# 2017_IHM.net
KiCad netlist of a schematic drawn in Altium Designer
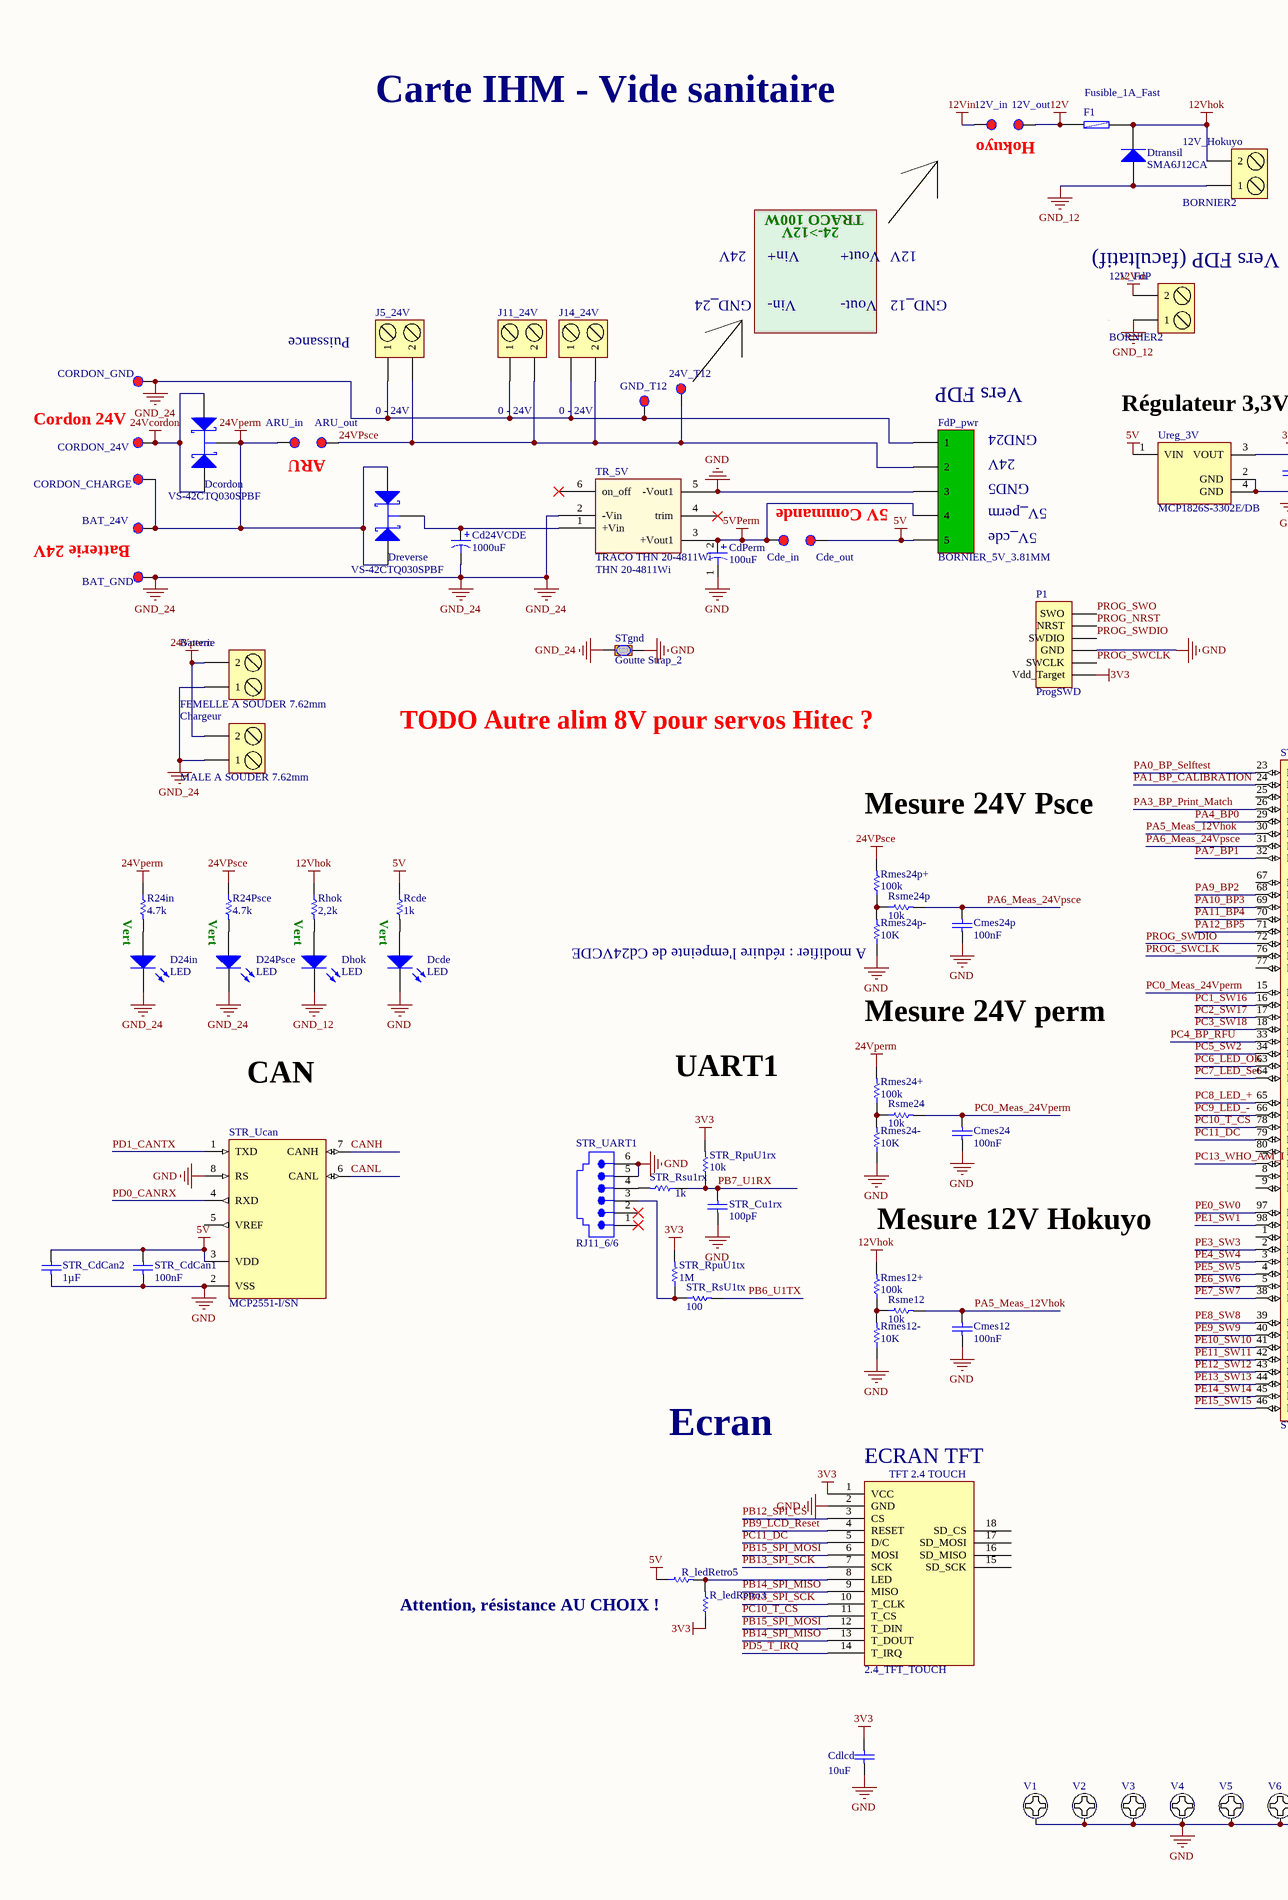
[diagram p0: 2017_IHM.SchDoc, left]
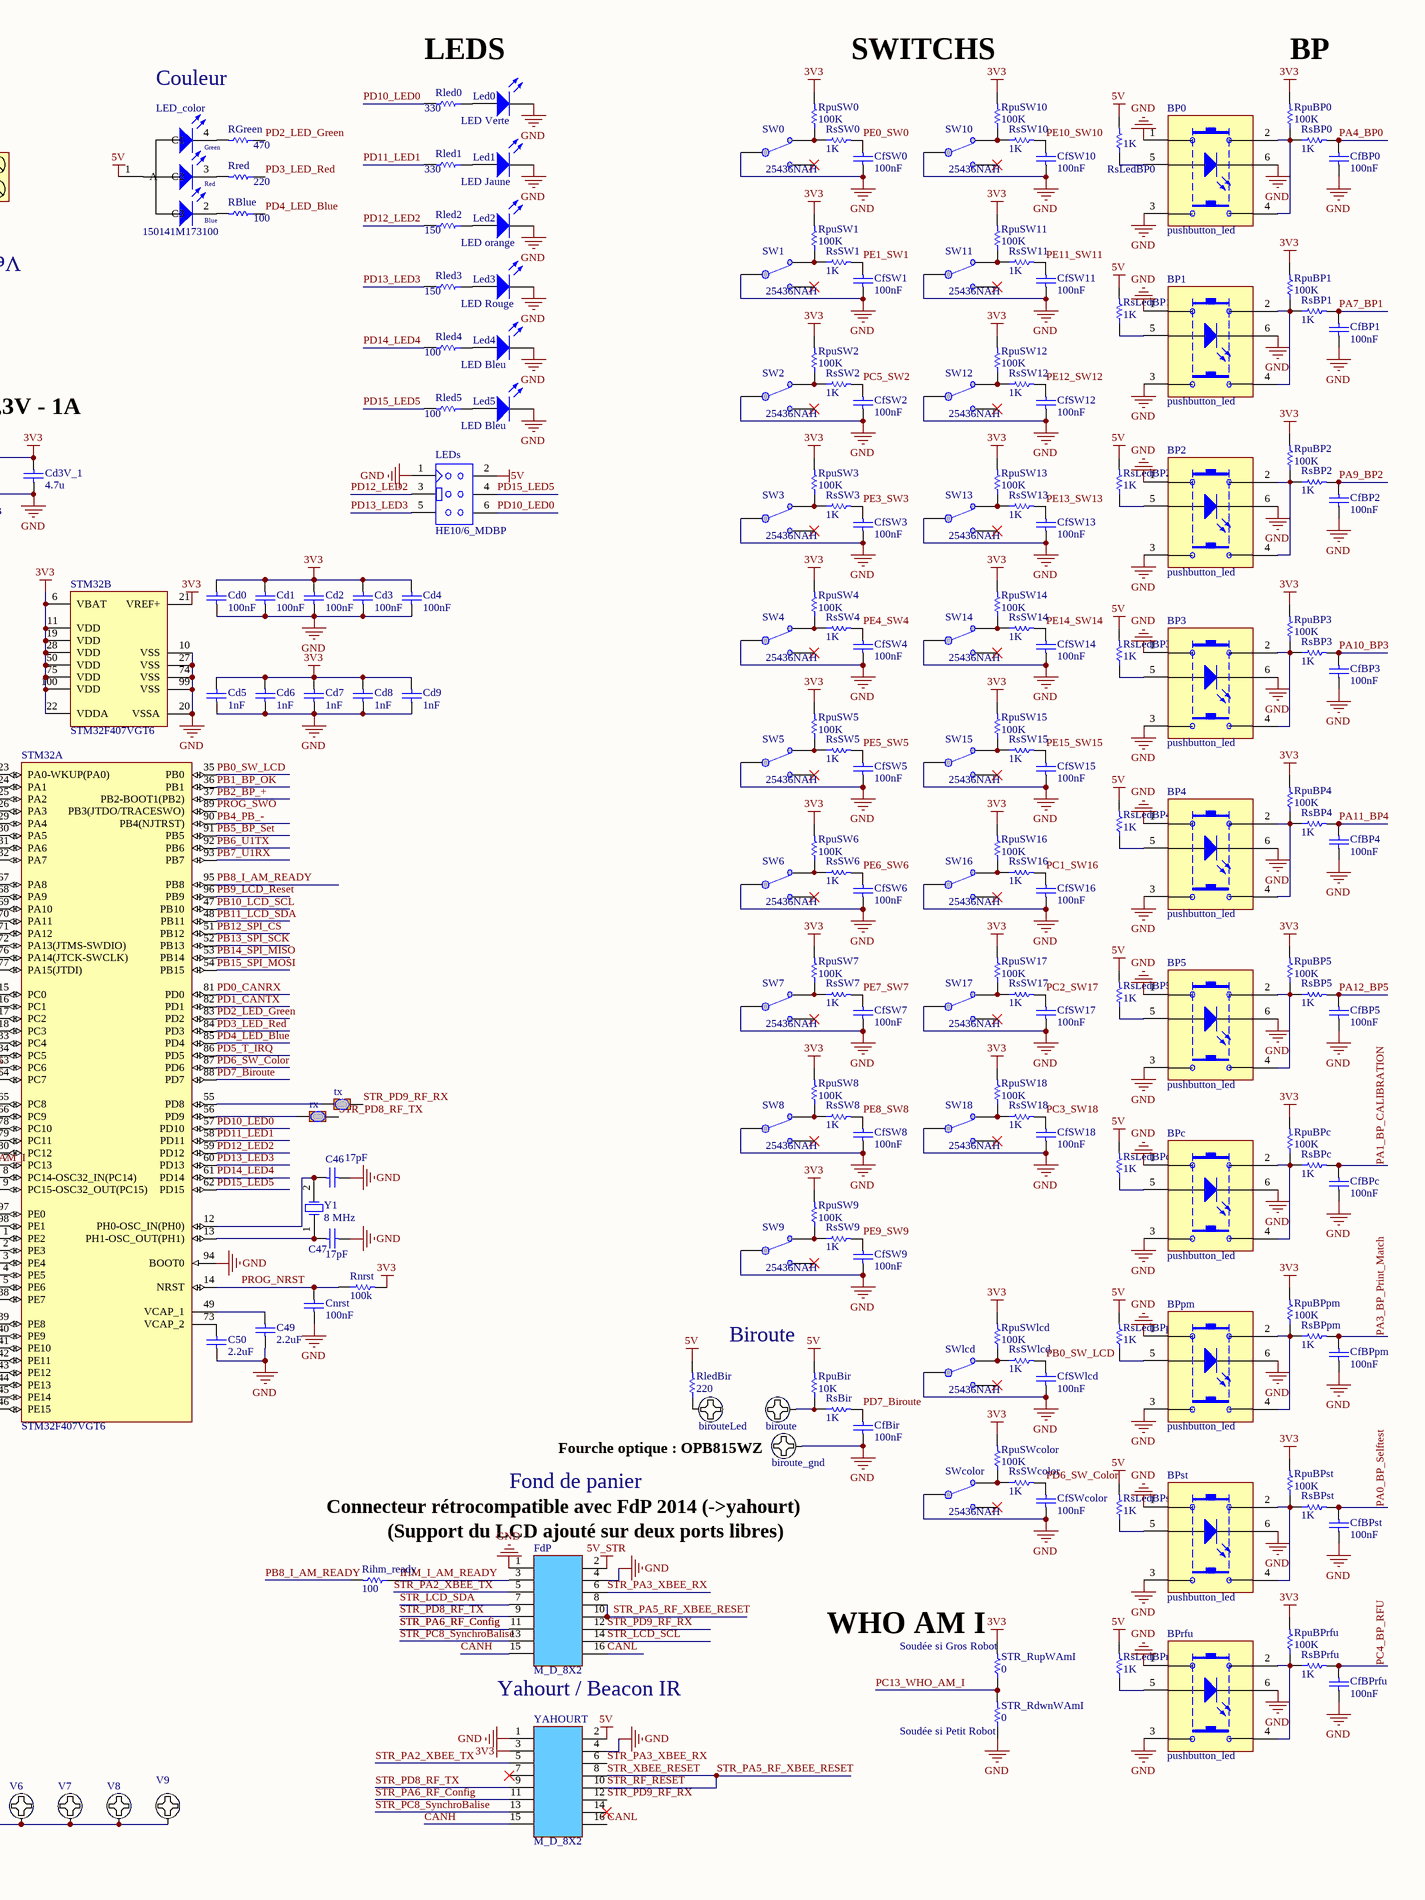
[diagram p1: 2017_IHM.SchDoc, right]

(export (version "E")
  (design (tool "Eeschema 10.0.6"))
  (components
    (comp (ref "*")
      (value "2.4_TFT_TOUCH")
      (footprint "2.4_TFT_TOUCH")
      (libsource (lib "_ROBOT") (part "2.4_TFT_TOUCH"))
    )
    (comp (ref "12V_FdP")
      (value "BORNIER2")
      (footprint "BORNIER2")
      (description "Terminal blocks, 2 pins, pitch=5mm")
      (libsource (lib "Connecteur") (part "BORNIER2"))
    )
    (comp (ref "12V_Hokuyo")
      (value "BORNIER2")
      (footprint "BORNIER2_HORIZ")
      (description "Terminal blocks, 2 pins, pitch=5mm")
      (libsource (lib "Connecteur") (part "BORNIER2"))
    )
    (comp (ref "12V_in")
      (value "Name")
      (footprint "Point Test_D3_P1.6mm")
      (description "Point test")
      (fields (field (name "PUBLISHER") "Damien GUITTON"))
      (libsource (lib "DG_Connecteur") (part "Point Test"))
    )
    (comp (ref "12V_out")
      (value "Name")
      (footprint "Point Test_D3_P1.6mm")
      (description "Point test")
      (fields (field (name "PUBLISHER") "Damien GUITTON"))
      (libsource (lib "DG_Connecteur") (part "Point Test"))
    )
    (comp (ref "24V_T12")
      (value "Name")
      (footprint "Point Test_D3_P1.6mm")
      (description "Point test")
      (fields (field (name "PUBLISHER") "Damien GUITTON"))
      (libsource (lib "DG_Connecteur") (part "Point Test"))
    )
    (comp (ref "ARU_in")
      (value "Name")
      (footprint "Point Test_D3_P1.6mm")
      (description "Point test")
      (fields (field (name "PUBLISHER") "Damien GUITTON"))
      (libsource (lib "DG_Connecteur") (part "Point Test"))
    )
    (comp (ref "ARU_out")
      (value "Name")
      (footprint "Point Test_D3_P1.6mm")
      (description "Point test")
      (fields (field (name "PUBLISHER") "Damien GUITTON"))
      (libsource (lib "DG_Connecteur") (part "Point Test"))
    )
    (comp (ref "Batterie")
      (value "FEMELLE A SOUDER 7.62mm")
      (footprint "BORNIER2_FEM_COUDE")
      (description "Terminal blocks, 2 pins, pitch=5mm")
      (libsource (lib "Connecteur") (part "BORNIER2"))
    )
    (comp (ref "BAT_24V")
      (value "Name")
      (footprint "Point Test_D3_P1.6mm")
      (description "Point test")
      (fields (field (name "PUBLISHER") "Damien GUITTON"))
      (libsource (lib "DG_Connecteur") (part "Point Test"))
    )
    (comp (ref "BAT_GND")
      (value "Name")
      (footprint "Point Test_D3_P1.6mm")
      (description "Point test")
      (fields (field (name "PUBLISHER") "Damien GUITTON"))
      (libsource (lib "DG_Connecteur") (part "Point Test"))
    )
    (comp (ref "biroute")
      (value "Pad_M3")
      (footprint "PAD_CMS_5.08x2.54")
      (description "Vis M3 X 6mm _TORX_Tête 6mm")
      (fields (field (name "PUBLISHER") "Damien Guitton"))
      (libsource (lib "_ROBOT") (part "Vis M3 X 6mm _TORX_Tête 6mm"))
    )
    (comp (ref "birouteLed")
      (value "Pad_M3")
      (footprint "PAD_CMS_5.08x2.54")
      (description "Vis M3 X 6mm _TORX_Tête 6mm")
      (fields (field (name "PUBLISHER") "Damien Guitton"))
      (libsource (lib "_ROBOT") (part "Vis M3 X 6mm _TORX_Tête 6mm"))
    )
    (comp (ref "biroute_gnd")
      (value "Pad_M3")
      (footprint "PAD_CMS_5.08x2.54")
      (description "Vis M3 X 6mm _TORX_Tête 6mm")
      (fields (field (name "PUBLISHER") "Damien Guitton"))
      (libsource (lib "_ROBOT") (part "Vis M3 X 6mm _TORX_Tête 6mm"))
    )
    (comp (ref "BP0")
      (value "pushbutton_led")
      (footprint "PUSHBUTTON_LED")
      (libsource (lib "_ROBOT") (part "pushbutton_led"))
    )
    (comp (ref "BP1")
      (value "pushbutton_led")
      (footprint "PUSHBUTTON_LED")
      (libsource (lib "_ROBOT") (part "pushbutton_led"))
    )
    (comp (ref "BP2")
      (value "pushbutton_led")
      (footprint "PUSHBUTTON_LED")
      (libsource (lib "_ROBOT") (part "pushbutton_led"))
    )
    (comp (ref "BP3")
      (value "pushbutton_led")
      (footprint "PUSHBUTTON_LED")
      (libsource (lib "_ROBOT") (part "pushbutton_led"))
    )
    (comp (ref "BP4")
      (value "pushbutton_led")
      (footprint "PUSHBUTTON_LED")
      (libsource (lib "_ROBOT") (part "pushbutton_led"))
    )
    (comp (ref "BP5")
      (value "pushbutton_led")
      (footprint "PUSHBUTTON_LED")
      (libsource (lib "_ROBOT") (part "pushbutton_led"))
    )
    (comp (ref "BPc")
      (value "pushbutton_led")
      (footprint "PUSHBUTTON_LED")
      (libsource (lib "_ROBOT") (part "pushbutton_led"))
    )
    (comp (ref "BPpm")
      (value "pushbutton_led")
      (footprint "PUSHBUTTON_LED")
      (libsource (lib "_ROBOT") (part "pushbutton_led"))
    )
    (comp (ref "BPrfu")
      (value "pushbutton_led")
      (footprint "PUSHBUTTON_LED")
      (libsource (lib "_ROBOT") (part "pushbutton_led"))
    )
    (comp (ref "BPst")
      (value "pushbutton_led")
      (footprint "PUSHBUTTON_LED")
      (libsource (lib "_ROBOT") (part "pushbutton_led"))
    )
    (comp (ref "C46")
      (value "17pF")
      (footprint "C0805_N")
      (description "Capacitor")
      (fields (field (name "PUBLISHER") "Altium Limited"))
      (libsource (lib "_ROBOT") (part "Condensateur"))
    )
    (comp (ref "C47")
      (value "17pF")
      (footprint "C0805_N")
      (description "Capacitor")
      (fields (field (name "PUBLISHER") "Altium Limited"))
      (libsource (lib "_ROBOT") (part "Condensateur"))
    )
    (comp (ref "C49")
      (value "2.2uF")
      (footprint "C0805_N")
      (description "Capacitor")
      (fields (field (name "PUBLISHER") "Altium Limited"))
      (libsource (lib "_ROBOT") (part "Condensateur"))
    )
    (comp (ref "C50")
      (value "2.2uF")
      (footprint "C0805_N")
      (description "Capacitor")
      (fields (field (name "PUBLISHER") "Altium Limited"))
      (libsource (lib "_ROBOT") (part "Condensateur"))
    )
    (comp (ref "Cd0")
      (value "100nF")
      (footprint "C0805_N")
      (description "Capacitor")
      (fields (field (name "PUBLISHER") "Altium Limited"))
      (libsource (lib "_ROBOT") (part "Condensateur"))
    )
    (comp (ref "Cd1")
      (value "100nF")
      (footprint "C0805_N")
      (description "Capacitor")
      (fields (field (name "PUBLISHER") "Altium Limited"))
      (libsource (lib "_ROBOT") (part "Condensateur"))
    )
    (comp (ref "Cd2")
      (value "100nF")
      (footprint "C0805_N")
      (description "Capacitor")
      (fields (field (name "PUBLISHER") "Altium Limited"))
      (libsource (lib "_ROBOT") (part "Condensateur"))
    )
    (comp (ref "Cd3")
      (value "100nF")
      (footprint "C0805_N")
      (description "Capacitor")
      (fields (field (name "PUBLISHER") "Altium Limited"))
      (libsource (lib "_ROBOT") (part "Condensateur"))
    )
    (comp (ref "Cd3V_1")
      (value "4.7u")
      (footprint "C0805_N")
      (description "Capacitor")
      (fields (field (name "PUBLISHER") "Altium Limited"))
      (libsource (lib "DG_Condensateur") (part "Capacitor"))
    )
    (comp (ref "Cd4")
      (value "100nF")
      (footprint "C0805_N")
      (description "Capacitor")
      (fields (field (name "PUBLISHER") "Altium Limited"))
      (libsource (lib "_ROBOT") (part "Condensateur"))
    )
    (comp (ref "Cd5")
      (value "1nF")
      (footprint "C0805_N")
      (description "Capacitor")
      (fields (field (name "PUBLISHER") "Altium Limited"))
      (libsource (lib "_ROBOT") (part "Condensateur"))
    )
    (comp (ref "Cd6")
      (value "1nF")
      (footprint "C0805_N")
      (description "Capacitor")
      (fields (field (name "PUBLISHER") "Altium Limited"))
      (libsource (lib "_ROBOT") (part "Condensateur"))
    )
    (comp (ref "Cd7")
      (value "1nF")
      (footprint "C0805_N")
      (description "Capacitor")
      (fields (field (name "PUBLISHER") "Altium Limited"))
      (libsource (lib "_ROBOT") (part "Condensateur"))
    )
    (comp (ref "Cd8")
      (value "1nF")
      (footprint "C0805_N")
      (description "Capacitor")
      (fields (field (name "PUBLISHER") "Altium Limited"))
      (libsource (lib "_ROBOT") (part "Condensateur"))
    )
    (comp (ref "Cd9")
      (value "1nF")
      (footprint "C0805_N")
      (description "Capacitor")
      (fields (field (name "PUBLISHER") "Altium Limited"))
      (libsource (lib "_ROBOT") (part "Condensateur"))
    )
    (comp (ref "Cd24VCDE")
      (value "1000uF")
      (footprint "RESISTANCE_5W")
      (description "Polarized Capacitor")
      (libsource (lib "_ROBOT") (part "Condensateur Polarise Traversant"))
    )
    (comp (ref "Cde_in")
      (value "Name")
      (footprint "Point Test_D3_P1.6mm")
      (description "Point test")
      (fields (field (name "PUBLISHER") "Damien GUITTON"))
      (libsource (lib "DG_Connecteur") (part "Point Test"))
    )
    (comp (ref "Cde_out")
      (value "Name")
      (footprint "Point Test_D3_P1.6mm")
      (description "Point test")
      (fields (field (name "PUBLISHER") "Damien GUITTON"))
      (libsource (lib "DG_Connecteur") (part "Point Test"))
    )
    (comp (ref "Cdlcd")
      (value "10uF")
      (footprint "C0805_N")
      (description "Capacitor")
      (fields (field (name "PUBLISHER") "Altium Limited"))
      (libsource (lib "_ROBOT") (part "Condensateur"))
    )
    (comp (ref "CdPerm")
      (value "100uF")
      (footprint "CONDENSATEUR_POLARISE_ELECTROLYTIQUE_RADIAL_5.08/8.9")
      (description "Polarized Capacitor")
      (libsource (lib "") (part "Condensateur Polarise Traversant_1"))
    )
    (comp (ref "CfBir")
      (value "100nF")
      (footprint "C0805_N")
      (description "Capacitor")
      (fields (field (name "PUBLISHER") "Altium Limited"))
      (libsource (lib "_ROBOT") (part "Condensateur"))
    )
    (comp (ref "CfBP0")
      (value "100nF")
      (footprint "C0805_N")
      (description "Capacitor")
      (fields (field (name "PUBLISHER") "Altium Limited"))
      (libsource (lib "_ROBOT") (part "Condensateur"))
    )
    (comp (ref "CfBP1")
      (value "100nF")
      (footprint "C0805_N")
      (description "Capacitor")
      (fields (field (name "PUBLISHER") "Altium Limited"))
      (libsource (lib "_ROBOT") (part "Condensateur"))
    )
    (comp (ref "CfBP2")
      (value "100nF")
      (footprint "C0805_N")
      (description "Capacitor")
      (fields (field (name "PUBLISHER") "Altium Limited"))
      (libsource (lib "_ROBOT") (part "Condensateur"))
    )
    (comp (ref "CfBP3")
      (value "100nF")
      (footprint "C0805_N")
      (description "Capacitor")
      (fields (field (name "PUBLISHER") "Altium Limited"))
      (libsource (lib "_ROBOT") (part "Condensateur"))
    )
    (comp (ref "CfBP4")
      (value "100nF")
      (footprint "C0805_N")
      (description "Capacitor")
      (fields (field (name "PUBLISHER") "Altium Limited"))
      (libsource (lib "_ROBOT") (part "Condensateur"))
    )
    (comp (ref "CfBP5")
      (value "100nF")
      (footprint "C0805_N")
      (description "Capacitor")
      (fields (field (name "PUBLISHER") "Altium Limited"))
      (libsource (lib "_ROBOT") (part "Condensateur"))
    )
    (comp (ref "CfBPc")
      (value "100nF")
      (footprint "C0805_N")
      (description "Capacitor")
      (fields (field (name "PUBLISHER") "Altium Limited"))
      (libsource (lib "_ROBOT") (part "Condensateur"))
    )
    (comp (ref "CfBPpm")
      (value "100nF")
      (footprint "C0805_N")
      (description "Capacitor")
      (fields (field (name "PUBLISHER") "Altium Limited"))
      (libsource (lib "_ROBOT") (part "Condensateur"))
    )
    (comp (ref "CfBPrfu")
      (value "100nF")
      (footprint "C0805_N")
      (description "Capacitor")
      (fields (field (name "PUBLISHER") "Altium Limited"))
      (libsource (lib "_ROBOT") (part "Condensateur"))
    )
    (comp (ref "CfBPst")
      (value "100nF")
      (footprint "C0805_N")
      (description "Capacitor")
      (fields (field (name "PUBLISHER") "Altium Limited"))
      (libsource (lib "_ROBOT") (part "Condensateur"))
    )
    (comp (ref "CfSW0")
      (value "100nF")
      (footprint "C0805_N")
      (description "Capacitor")
      (fields (field (name "PUBLISHER") "Altium Limited"))
      (libsource (lib "_ROBOT") (part "Condensateur"))
    )
    (comp (ref "CfSW1")
      (value "100nF")
      (footprint "C0805_N")
      (description "Capacitor")
      (fields (field (name "PUBLISHER") "Altium Limited"))
      (libsource (lib "_ROBOT") (part "Condensateur"))
    )
    (comp (ref "CfSW2")
      (value "100nF")
      (footprint "C0805_N")
      (description "Capacitor")
      (fields (field (name "PUBLISHER") "Altium Limited"))
      (libsource (lib "_ROBOT") (part "Condensateur"))
    )
    (comp (ref "CfSW3")
      (value "100nF")
      (footprint "C0805_N")
      (description "Capacitor")
      (fields (field (name "PUBLISHER") "Altium Limited"))
      (libsource (lib "_ROBOT") (part "Condensateur"))
    )
    (comp (ref "CfSW4")
      (value "100nF")
      (footprint "C0805_N")
      (description "Capacitor")
      (fields (field (name "PUBLISHER") "Altium Limited"))
      (libsource (lib "_ROBOT") (part "Condensateur"))
    )
    (comp (ref "CfSW5")
      (value "100nF")
      (footprint "C0805_N")
      (description "Capacitor")
      (fields (field (name "PUBLISHER") "Altium Limited"))
      (libsource (lib "_ROBOT") (part "Condensateur"))
    )
    (comp (ref "CfSW6")
      (value "100nF")
      (footprint "C0805_N")
      (description "Capacitor")
      (fields (field (name "PUBLISHER") "Altium Limited"))
      (libsource (lib "_ROBOT") (part "Condensateur"))
    )
    (comp (ref "CfSW7")
      (value "100nF")
      (footprint "C0805_N")
      (description "Capacitor")
      (fields (field (name "PUBLISHER") "Altium Limited"))
      (libsource (lib "_ROBOT") (part "Condensateur"))
    )
    (comp (ref "CfSW8")
      (value "100nF")
      (footprint "C0805_N")
      (description "Capacitor")
      (fields (field (name "PUBLISHER") "Altium Limited"))
      (libsource (lib "_ROBOT") (part "Condensateur"))
    )
    (comp (ref "CfSW9")
      (value "100nF")
      (footprint "C0805_N")
      (description "Capacitor")
      (fields (field (name "PUBLISHER") "Altium Limited"))
      (libsource (lib "_ROBOT") (part "Condensateur"))
    )
    (comp (ref "CfSW10")
      (value "100nF")
      (footprint "C0805_N")
      (description "Capacitor")
      (fields (field (name "PUBLISHER") "Altium Limited"))
      (libsource (lib "_ROBOT") (part "Condensateur"))
    )
    (comp (ref "CfSW11")
      (value "100nF")
      (footprint "C0805_N")
      (description "Capacitor")
      (fields (field (name "PUBLISHER") "Altium Limited"))
      (libsource (lib "_ROBOT") (part "Condensateur"))
    )
    (comp (ref "CfSW12")
      (value "100nF")
      (footprint "C0805_N")
      (description "Capacitor")
      (fields (field (name "PUBLISHER") "Altium Limited"))
      (libsource (lib "_ROBOT") (part "Condensateur"))
    )
    (comp (ref "CfSW13")
      (value "100nF")
      (footprint "C0805_N")
      (description "Capacitor")
      (fields (field (name "PUBLISHER") "Altium Limited"))
      (libsource (lib "_ROBOT") (part "Condensateur"))
    )
    (comp (ref "CfSW14")
      (value "100nF")
      (footprint "C0805_N")
      (description "Capacitor")
      (fields (field (name "PUBLISHER") "Altium Limited"))
      (libsource (lib "_ROBOT") (part "Condensateur"))
    )
    (comp (ref "CfSW15")
      (value "100nF")
      (footprint "C0805_N")
      (description "Capacitor")
      (fields (field (name "PUBLISHER") "Altium Limited"))
      (libsource (lib "_ROBOT") (part "Condensateur"))
    )
    (comp (ref "CfSW16")
      (value "100nF")
      (footprint "C0805_N")
      (description "Capacitor")
      (fields (field (name "PUBLISHER") "Altium Limited"))
      (libsource (lib "_ROBOT") (part "Condensateur"))
    )
    (comp (ref "CfSW17")
      (value "100nF")
      (footprint "C0805_N")
      (description "Capacitor")
      (fields (field (name "PUBLISHER") "Altium Limited"))
      (libsource (lib "_ROBOT") (part "Condensateur"))
    )
    (comp (ref "CfSW18")
      (value "100nF")
      (footprint "C0805_N")
      (description "Capacitor")
      (fields (field (name "PUBLISHER") "Altium Limited"))
      (libsource (lib "_ROBOT") (part "Condensateur"))
    )
    (comp (ref "CfSWcolor")
      (value "100nF")
      (footprint "C0805_N")
      (description "Capacitor")
      (fields (field (name "PUBLISHER") "Altium Limited"))
      (libsource (lib "_ROBOT") (part "Condensateur"))
    )
    (comp (ref "CfSWlcd")
      (value "100nF")
      (footprint "C0805_N")
      (description "Capacitor")
      (fields (field (name "PUBLISHER") "Altium Limited"))
      (libsource (lib "_ROBOT") (part "Condensateur"))
    )
    (comp (ref "Chargeur")
      (value "MALE A SOUDER 7.62mm")
      (footprint "BORNIER2_FEM_COUDE")
      (description "Terminal blocks, 2 pins, pitch=5mm")
      (libsource (lib "Connecteur") (part "BORNIER2"))
    )
    (comp (ref "Cmes12")
      (value "100nF")
      (footprint "C0805_N")
      (description "Capacitor")
      (fields (field (name "PUBLISHER") "Altium Limited"))
      (libsource (lib "_ROBOT") (part "Condensateur"))
    )
    (comp (ref "Cmes24")
      (value "100nF")
      (footprint "C0805_N")
      (description "Capacitor")
      (fields (field (name "PUBLISHER") "Altium Limited"))
      (libsource (lib "_ROBOT") (part "Condensateur"))
    )
    (comp (ref "Cmes24p")
      (value "100nF")
      (footprint "C0805_N")
      (description "Capacitor")
      (fields (field (name "PUBLISHER") "Altium Limited"))
      (libsource (lib "_ROBOT") (part "Condensateur"))
    )
    (comp (ref "Cnrst")
      (value "100nF")
      (footprint "C0805_N")
      (description "Capacitor")
      (fields (field (name "PUBLISHER") "Altium Limited"))
      (libsource (lib "_ROBOT") (part "Condensateur"))
    )
    (comp (ref "CORDON_24V")
      (value "Name")
      (footprint "Point Test_D3_P1.6mm")
      (description "Point test")
      (fields (field (name "PUBLISHER") "Damien GUITTON"))
      (libsource (lib "DG_Connecteur") (part "Point Test"))
    )
    (comp (ref "CORDON_CHARGE")
      (value "Name")
      (footprint "Point Test_D3_P1.6mm")
      (description "Point test")
      (fields (field (name "PUBLISHER") "Damien GUITTON"))
      (libsource (lib "DG_Connecteur") (part "Point Test"))
    )
    (comp (ref "CORDON_GND")
      (value "Name")
      (footprint "Point Test_D3_P1.6mm")
      (description "Point test")
      (fields (field (name "PUBLISHER") "Damien GUITTON"))
      (libsource (lib "DG_Connecteur") (part "Point Test"))
    )
    (comp (ref "D24in")
      (value "LED")
      (footprint "LED_0805")
      (description "Typical LED")
      (fields (field (name "PUBLISHER") "Altium Limited"))
      (libsource (lib "_ROBOT") (part "LED"))
    )
    (comp (ref "D24Psce")
      (value "LED")
      (footprint "LED_0805")
      (description "Typical LED")
      (fields (field (name "PUBLISHER") "Altium Limited"))
      (libsource (lib "_ROBOT") (part "LED"))
    )
    (comp (ref "Dcde")
      (value "LED")
      (footprint "LED_0805")
      (description "Typical LED")
      (fields (field (name "PUBLISHER") "Altium Limited"))
      (libsource (lib "_ROBOT") (part "LED"))
    )
    (comp (ref "Dcordon")
      (value "VS-42CTQ030SPBF")
      (footprint "D2Pak (123)")
      (description "DIODE SCHOTTKY DOUBLE")
      (fields (field (name "MANUFACTURER PART NUMBER") "BAT54C") (field (name "MANUFACTURER") "ZETEX"))
      (libsource (lib "_ROBOT") (part "Diode Shottky double BAT54C"))
    )
    (comp (ref "Dhok")
      (value "LED")
      (footprint "LED_0805")
      (description "Typical LED")
      (fields (field (name "PUBLISHER") "Altium Limited"))
      (libsource (lib "_ROBOT") (part "LED"))
    )
    (comp (ref "Dreverse")
      (value "VS-42CTQ030SPBF")
      (footprint "D2Pak (123)")
      (description "DIODE SCHOTTKY DOUBLE")
      (fields (field (name "MANUFACTURER PART NUMBER") "BAT54C") (field (name "MANUFACTURER") "ZETEX"))
      (libsource (lib "_ROBOT") (part "Diode Shottky double BAT54C"))
    )
    (comp (ref "Dtransil")
      (value "SMA6J12CA")
      (footprint "DO214AC")
      (description "1 Amp General Purpose Rectifier")
      (fields (field (name "PUBLISHER") "Altium Limited"))
      (libsource (lib "Miscellaneous Devices") (part "Diode 1N4001"))
    )
    (comp (ref "F1")
      (value "Fusible_1A_Fast")
      (footprint "R0805_N")
      (description "Fuse")
      (fields (field (name "PUBLISHER") "Altium Limited"))
      (libsource (lib "DG_Fusible") (part "Fusible_SMD"))
    )
    (comp (ref "FdP")
      (value "BARRETTE_8 CONTACTS_2 RANGEES_MALE_DROITE")
      (footprint "HE10/16_M_D_B P")
      (fields (field (name "TYPE") "M_D_8X2"))
      (libsource (lib "connecteurs") (part "BARRETTE_8 CONTACTS_2 RANGEES_MALE_DROITE"))
    )
    (comp (ref "FdP_pwr")
      (value "BORNIER_5V_3.81MM")
      (footprint "BORNIER_5V_3.5MM_femelle_0")
      (libsource (lib "Connecteur") (part "BORNIER_5V_3.81MM"))
    )
    (comp (ref "GND_T12")
      (value "Name")
      (footprint "Point Test_D3_P1.6mm")
      (description "Point test")
      (fields (field (name "PUBLISHER") "Damien GUITTON"))
      (libsource (lib "DG_Connecteur") (part "Point Test"))
    )
    (comp (ref "J5_24V")
      (value "0 - 24V")
      (footprint "BORNIER2_FEM_COUDE")
      (description "Terminal blocks, 2 pins, pitch=5mm")
      (libsource (lib "miniprojet") (part "BORNIER2"))
    )
    (comp (ref "J11_24V")
      (value "0 - 24V")
      (footprint "BORNIER2_FEM_COUDE")
      (description "Terminal blocks, 2 pins, pitch=5mm")
      (libsource (lib "miniprojet") (part "BORNIER2"))
    )
    (comp (ref "J14_24V")
      (value "0 - 24V")
      (footprint "BORNIER2_FEM_COUDE")
      (description "Terminal blocks, 2 pins, pitch=5mm")
      (libsource (lib "miniprojet") (part "BORNIER2"))
    )
    (comp (ref "Led0")
      (value "LED Verte")
      (footprint "LED_0805")
      (description "Typical LED")
      (fields (field (name "PUBLISHER") "Altium Limited"))
      (libsource (lib "DG_LED") (part "LED"))
    )
    (comp (ref "Led1")
      (value "LED Jaune")
      (footprint "LED_0805")
      (description "Typical LED")
      (fields (field (name "PUBLISHER") "Altium Limited"))
      (libsource (lib "DG_LED") (part "LED"))
    )
    (comp (ref "Led2")
      (value "LED orange")
      (footprint "LED_0805")
      (description "Typical LED")
      (fields (field (name "PUBLISHER") "Altium Limited"))
      (libsource (lib "DG_LED") (part "LED"))
    )
    (comp (ref "Led3")
      (value "LED Rouge")
      (footprint "LED_0805")
      (description "Typical LED")
      (fields (field (name "PUBLISHER") "Altium Limited"))
      (libsource (lib "DG_LED") (part "LED"))
    )
    (comp (ref "Led4")
      (value "LED Bleu")
      (footprint "LED_0805")
      (description "Typical LED")
      (fields (field (name "PUBLISHER") "Altium Limited"))
      (libsource (lib "DG_LED") (part "LED"))
    )
    (comp (ref "Led5")
      (value "LED Bleu")
      (footprint "LED_0805")
      (description "Typical LED")
      (fields (field (name "PUBLISHER") "Altium Limited"))
      (libsource (lib "DG_LED") (part "LED"))
    )
    (comp (ref "LEDs")
      (value "HE10/6_MALE_DROIT_BAS PROFIL")
      (footprint "HE10/6_M_D_BP")
      (description "EMBASE HE10/6 MALE DROIT BAS PROFIL")
      (fields (field (name "TYPE") "HE10/6_MDBP"))
      (libsource (lib "connecteurs") (part "HE10/6_MALE_DROIT_BAS PROFIL"))
    )
    (comp (ref "LED_color")
      (value "150141M173100")
      (footprint "3528")
      (description "SMD Full-Color Top LED, WL-SFTW, Red & Green & Blue")
      (fields
        (field (name "MANUFACTURER") "Würth Elektronik eiSos GmbH")
        (field (name "CREATED BY") "Christin Otto")
      )
      (libsource (lib "WL-SFTW") (part "WL-SFTW 3528 150141M173100"))
    )
    (comp (ref "P1")
      (value "ProgSWD")
      (footprint "HDR1X6")
      (description "Header, 6-Pin")
      (fields (field (name "PUBLISHER") "Altium Limited"))
      (libsource (lib "DG_Connecteur") (part "Header 6"))
    )
    (comp (ref "R24in")
      (value "4.7k")
      (footprint "R1206_N")
      (description "Resistor")
      (fields (field (name "PUBLISHER") "Altium Limited"))
      (libsource (lib "_ROBOT") (part "Resistor"))
    )
    (comp (ref "R24Psce")
      (value "4.7k")
      (footprint "R1206_N")
      (description "Resistor")
      (fields (field (name "PUBLISHER") "Altium Limited"))
      (libsource (lib "_ROBOT") (part "Resistor"))
    )
    (comp (ref "RBlue")
      (value "100")
      (footprint "R1206_N")
      (description "Resistor")
      (fields (field (name "PUBLISHER") "Altium Limited"))
      (libsource (lib "_ROBOT") (part "Resistor"))
    )
    (comp (ref "Rcde")
      (value "1k")
      (footprint "R1206_N")
      (description "Resistor")
      (fields (field (name "PUBLISHER") "Altium Limited"))
      (libsource (lib "_ROBOT") (part "Resistor"))
    )
    (comp (ref "RGreen")
      (value "470")
      (footprint "R1206_N")
      (description "Resistor")
      (fields (field (name "PUBLISHER") "Altium Limited"))
      (libsource (lib "_ROBOT") (part "Resistor"))
    )
    (comp (ref "Rhok")
      (value "2,2k")
      (footprint "R1206_N")
      (description "Resistor")
      (fields (field (name "PUBLISHER") "Altium Limited"))
      (libsource (lib "_ROBOT") (part "Resistor"))
    )
    (comp (ref "Rihm_ready")
      (value "100")
      (footprint "R1206_N")
      (description "Resistor")
      (fields (field (name "PUBLISHER") "Altium Limited"))
      (libsource (lib "_ROBOT") (part "Resistor"))
    )
    (comp (ref "Rled0")
      (value "330")
      (footprint "R1206_N")
      (description "Resistor")
      (fields (field (name "PUBLISHER") "Altium Limited"))
      (libsource (lib "_ROBOT") (part "Resistor"))
    )
    (comp (ref "Rled1")
      (value "330")
      (footprint "R1206_N")
      (description "Resistor")
      (fields (field (name "PUBLISHER") "Altium Limited"))
      (libsource (lib "_ROBOT") (part "Resistor"))
    )
    (comp (ref "Rled2")
      (value "150")
      (footprint "R1206_N")
      (description "Resistor")
      (fields (field (name "PUBLISHER") "Altium Limited"))
      (libsource (lib "_ROBOT") (part "Resistor"))
    )
    (comp (ref "Rled3")
      (value "150")
      (footprint "R1206_N")
      (description "Resistor")
      (fields (field (name "PUBLISHER") "Altium Limited"))
      (libsource (lib "_ROBOT") (part "Resistor"))
    )
    (comp (ref "Rled4")
      (value "100")
      (footprint "R1206_N")
      (description "Resistor")
      (fields (field (name "PUBLISHER") "Altium Limited"))
      (libsource (lib "_ROBOT") (part "Resistor"))
    )
    (comp (ref "Rled5")
      (value "100")
      (footprint "R1206_N")
      (description "Resistor")
      (fields (field (name "PUBLISHER") "Altium Limited"))
      (libsource (lib "_ROBOT") (part "Resistor"))
    )
    (comp (ref "RledBir")
      (value "220")
      (footprint "R1206_N")
      (description "Resistor")
      (fields (field (name "PUBLISHER") "Altium Limited"))
      (libsource (lib "_ROBOT") (part "Resistor"))
    )
    (comp (ref "Rmes12+")
      (value "100k")
      (footprint "R1206_N")
      (description "Resistor")
      (fields (field (name "PUBLISHER") "Altium Limited"))
      (libsource (lib "_ROBOT") (part "Resistor"))
    )
    (comp (ref "Rmes12-")
      (value "10K")
      (footprint "R1206_N")
      (description "Resistor")
      (fields (field (name "PUBLISHER") "Altium Limited"))
      (libsource (lib "_ROBOT") (part "Resistor"))
    )
    (comp (ref "Rmes24+")
      (value "100k")
      (footprint "R1206_N")
      (description "Resistor")
      (fields (field (name "PUBLISHER") "Altium Limited"))
      (libsource (lib "_ROBOT") (part "Resistor"))
    )
    (comp (ref "Rmes24-")
      (value "10K")
      (footprint "R1206_N")
      (description "Resistor")
      (fields (field (name "PUBLISHER") "Altium Limited"))
      (libsource (lib "_ROBOT") (part "Resistor"))
    )
    (comp (ref "Rmes24p+")
      (value "100k")
      (footprint "R1206_N")
      (description "Resistor")
      (fields (field (name "PUBLISHER") "Altium Limited"))
      (libsource (lib "_ROBOT") (part "Resistor"))
    )
    (comp (ref "Rmes24p-")
      (value "10K")
      (footprint "R1206_N")
      (description "Resistor")
      (fields (field (name "PUBLISHER") "Altium Limited"))
      (libsource (lib "_ROBOT") (part "Resistor"))
    )
    (comp (ref "Rnrst")
      (value "100k")
      (footprint "R1206_N")
      (description "Resistor")
      (fields (field (name "PUBLISHER") "Altium Limited"))
      (libsource (lib "_ROBOT") (part "Resistor"))
    )
    (comp (ref "RpuBir")
      (value "10K")
      (footprint "R1206_N")
      (description "Resistor")
      (fields (field (name "PUBLISHER") "Altium Limited"))
      (libsource (lib "_ROBOT") (part "Resistor"))
    )
    (comp (ref "RpuBP0")
      (value "100K")
      (footprint "R1206_N")
      (description "Resistor")
      (fields (field (name "PUBLISHER") "Altium Limited"))
      (libsource (lib "_ROBOT") (part "Resistor"))
    )
    (comp (ref "RpuBP1")
      (value "100K")
      (footprint "R1206_N")
      (description "Resistor")
      (fields (field (name "PUBLISHER") "Altium Limited"))
      (libsource (lib "_ROBOT") (part "Resistor"))
    )
    (comp (ref "RpuBP2")
      (value "100K")
      (footprint "R1206_N")
      (description "Resistor")
      (fields (field (name "PUBLISHER") "Altium Limited"))
      (libsource (lib "_ROBOT") (part "Resistor"))
    )
    (comp (ref "RpuBP3")
      (value "100K")
      (footprint "R1206_N")
      (description "Resistor")
      (fields (field (name "PUBLISHER") "Altium Limited"))
      (libsource (lib "_ROBOT") (part "Resistor"))
    )
    (comp (ref "RpuBP4")
      (value "100K")
      (footprint "R1206_N")
      (description "Resistor")
      (fields (field (name "PUBLISHER") "Altium Limited"))
      (libsource (lib "_ROBOT") (part "Resistor"))
    )
    (comp (ref "RpuBP5")
      (value "100K")
      (footprint "R1206_N")
      (description "Resistor")
      (fields (field (name "PUBLISHER") "Altium Limited"))
      (libsource (lib "_ROBOT") (part "Resistor"))
    )
    (comp (ref "RpuBPc")
      (value "100K")
      (footprint "R1206_N")
      (description "Resistor")
      (fields (field (name "PUBLISHER") "Altium Limited"))
      (libsource (lib "_ROBOT") (part "Resistor"))
    )
    (comp (ref "RpuBPpm")
      (value "100K")
      (footprint "R1206_N")
      (description "Resistor")
      (fields (field (name "PUBLISHER") "Altium Limited"))
      (libsource (lib "_ROBOT") (part "Resistor"))
    )
    (comp (ref "RpuBPrfu")
      (value "100K")
      (footprint "R1206_N")
      (description "Resistor")
      (fields (field (name "PUBLISHER") "Altium Limited"))
      (libsource (lib "_ROBOT") (part "Resistor"))
    )
    (comp (ref "RpuBPst")
      (value "100K")
      (footprint "R1206_N")
      (description "Resistor")
      (fields (field (name "PUBLISHER") "Altium Limited"))
      (libsource (lib "_ROBOT") (part "Resistor"))
    )
    (comp (ref "RpuSW0")
      (value "100K")
      (footprint "R1206_N")
      (description "Resistor")
      (fields (field (name "PUBLISHER") "Altium Limited"))
      (libsource (lib "_ROBOT") (part "Resistor"))
    )
    (comp (ref "RpuSW1")
      (value "100K")
      (footprint "R1206_N")
      (description "Resistor")
      (fields (field (name "PUBLISHER") "Altium Limited"))
      (libsource (lib "_ROBOT") (part "Resistor"))
    )
    (comp (ref "RpuSW2")
      (value "100K")
      (footprint "R1206_N")
      (description "Resistor")
      (fields (field (name "PUBLISHER") "Altium Limited"))
      (libsource (lib "_ROBOT") (part "Resistor"))
    )
    (comp (ref "RpuSW3")
      (value "100K")
      (footprint "R1206_N")
      (description "Resistor")
      (fields (field (name "PUBLISHER") "Altium Limited"))
      (libsource (lib "_ROBOT") (part "Resistor"))
    )
    (comp (ref "RpuSW4")
      (value "100K")
      (footprint "R1206_N")
      (description "Resistor")
      (fields (field (name "PUBLISHER") "Altium Limited"))
      (libsource (lib "_ROBOT") (part "Resistor"))
    )
    (comp (ref "RpuSW5")
      (value "100K")
      (footprint "R1206_N")
      (description "Resistor")
      (fields (field (name "PUBLISHER") "Altium Limited"))
      (libsource (lib "_ROBOT") (part "Resistor"))
    )
    (comp (ref "RpuSW6")
      (value "100K")
      (footprint "R1206_N")
      (description "Resistor")
      (fields (field (name "PUBLISHER") "Altium Limited"))
      (libsource (lib "_ROBOT") (part "Resistor"))
    )
    (comp (ref "RpuSW7")
      (value "100K")
      (footprint "R1206_N")
      (description "Resistor")
      (fields (field (name "PUBLISHER") "Altium Limited"))
      (libsource (lib "_ROBOT") (part "Resistor"))
    )
    (comp (ref "RpuSW8")
      (value "100K")
      (footprint "R1206_N")
      (description "Resistor")
      (fields (field (name "PUBLISHER") "Altium Limited"))
      (libsource (lib "_ROBOT") (part "Resistor"))
    )
    (comp (ref "RpuSW9")
      (value "100K")
      (footprint "R1206_N")
      (description "Resistor")
      (fields (field (name "PUBLISHER") "Altium Limited"))
      (libsource (lib "_ROBOT") (part "Resistor"))
    )
    (comp (ref "RpuSW10")
      (value "100K")
      (footprint "R1206_N")
      (description "Resistor")
      (fields (field (name "PUBLISHER") "Altium Limited"))
      (libsource (lib "_ROBOT") (part "Resistor"))
    )
    (comp (ref "RpuSW11")
      (value "100K")
      (footprint "R1206_N")
      (description "Resistor")
      (fields (field (name "PUBLISHER") "Altium Limited"))
      (libsource (lib "_ROBOT") (part "Resistor"))
    )
    (comp (ref "RpuSW12")
      (value "100K")
      (footprint "R1206_N")
      (description "Resistor")
      (fields (field (name "PUBLISHER") "Altium Limited"))
      (libsource (lib "_ROBOT") (part "Resistor"))
    )
    (comp (ref "RpuSW13")
      (value "100K")
      (footprint "R1206_N")
      (description "Resistor")
      (fields (field (name "PUBLISHER") "Altium Limited"))
      (libsource (lib "_ROBOT") (part "Resistor"))
    )
    (comp (ref "RpuSW14")
      (value "100K")
      (footprint "R1206_N")
      (description "Resistor")
      (fields (field (name "PUBLISHER") "Altium Limited"))
      (libsource (lib "_ROBOT") (part "Resistor"))
    )
    (comp (ref "RpuSW15")
      (value "100K")
      (footprint "R1206_N")
      (description "Resistor")
      (fields (field (name "PUBLISHER") "Altium Limited"))
      (libsource (lib "_ROBOT") (part "Resistor"))
    )
    (comp (ref "RpuSW16")
      (value "100K")
      (footprint "R1206_N")
      (description "Resistor")
      (fields (field (name "PUBLISHER") "Altium Limited"))
      (libsource (lib "_ROBOT") (part "Resistor"))
    )
    (comp (ref "RpuSW17")
      (value "100K")
      (footprint "R1206_N")
      (description "Resistor")
      (fields (field (name "PUBLISHER") "Altium Limited"))
      (libsource (lib "_ROBOT") (part "Resistor"))
    )
    (comp (ref "RpuSW18")
      (value "100K")
      (footprint "R1206_N")
      (description "Resistor")
      (fields (field (name "PUBLISHER") "Altium Limited"))
      (libsource (lib "_ROBOT") (part "Resistor"))
    )
    (comp (ref "RpuSWcolor")
      (value "100K")
      (footprint "R1206_N")
      (description "Resistor")
      (fields (field (name "PUBLISHER") "Altium Limited"))
      (libsource (lib "_ROBOT") (part "Resistor"))
    )
    (comp (ref "RpuSWlcd")
      (value "100K")
      (footprint "R1206_N")
      (description "Resistor")
      (fields (field (name "PUBLISHER") "Altium Limited"))
      (libsource (lib "_ROBOT") (part "Resistor"))
    )
    (comp (ref "Rred")
      (value "220")
      (footprint "R1206_N")
      (description "Resistor")
      (fields (field (name "PUBLISHER") "Altium Limited"))
      (libsource (lib "_ROBOT") (part "Resistor"))
    )
    (comp (ref "RsBir")
      (value "1K")
      (footprint "R1206_N")
      (description "Resistor")
      (fields (field (name "PUBLISHER") "Altium Limited"))
      (libsource (lib "_ROBOT") (part "Resistor"))
    )
    (comp (ref "RsBP0")
      (value "1K")
      (footprint "R1206_N")
      (description "Resistor")
      (fields (field (name "PUBLISHER") "Altium Limited"))
      (libsource (lib "_ROBOT") (part "Resistor"))
    )
    (comp (ref "RsBP1")
      (value "1K")
      (footprint "R1206_N")
      (description "Resistor")
      (fields (field (name "PUBLISHER") "Altium Limited"))
      (libsource (lib "_ROBOT") (part "Resistor"))
    )
    (comp (ref "RsBP2")
      (value "1K")
      (footprint "R1206_N")
      (description "Resistor")
      (fields (field (name "PUBLISHER") "Altium Limited"))
      (libsource (lib "_ROBOT") (part "Resistor"))
    )
    (comp (ref "RsBP3")
      (value "1K")
      (footprint "R1206_N")
      (description "Resistor")
      (fields (field (name "PUBLISHER") "Altium Limited"))
      (libsource (lib "_ROBOT") (part "Resistor"))
    )
    (comp (ref "RsBP4")
      (value "1K")
      (footprint "R1206_N")
      (description "Resistor")
      (fields (field (name "PUBLISHER") "Altium Limited"))
      (libsource (lib "_ROBOT") (part "Resistor"))
    )
    (comp (ref "RsBP5")
      (value "1K")
      (footprint "R1206_N")
      (description "Resistor")
      (fields (field (name "PUBLISHER") "Altium Limited"))
      (libsource (lib "_ROBOT") (part "Resistor"))
    )
    (comp (ref "RsBPc")
      (value "1K")
      (footprint "R1206_N")
      (description "Resistor")
      (fields (field (name "PUBLISHER") "Altium Limited"))
      (libsource (lib "_ROBOT") (part "Resistor"))
    )
    (comp (ref "RsBPpm")
      (value "1K")
      (footprint "R1206_N")
      (description "Resistor")
      (fields (field (name "PUBLISHER") "Altium Limited"))
      (libsource (lib "_ROBOT") (part "Resistor"))
    )
    (comp (ref "RsBPrfu")
      (value "1K")
      (footprint "R1206_N")
      (description "Resistor")
      (fields (field (name "PUBLISHER") "Altium Limited"))
      (libsource (lib "_ROBOT") (part "Resistor"))
    )
    (comp (ref "RsBPst")
      (value "1K")
      (footprint "R1206_N")
      (description "Resistor")
      (fields (field (name "PUBLISHER") "Altium Limited"))
      (libsource (lib "_ROBOT") (part "Resistor"))
    )
    (comp (ref "RsLedBP0")
      (value "1K")
      (footprint "R1206_N")
      (description "Resistor")
      (fields (field (name "PUBLISHER") "Altium Limited"))
      (libsource (lib "_ROBOT") (part "Resistor"))
    )
    (comp (ref "RsLedBP1")
      (value "1K")
      (footprint "R1206_N")
      (description "Resistor")
      (fields (field (name "PUBLISHER") "Altium Limited"))
      (libsource (lib "_ROBOT") (part "Resistor"))
    )
    (comp (ref "RsLedBP2")
      (value "1K")
      (footprint "R1206_N")
      (description "Resistor")
      (fields (field (name "PUBLISHER") "Altium Limited"))
      (libsource (lib "_ROBOT") (part "Resistor"))
    )
    (comp (ref "RsLedBP3")
      (value "1K")
      (footprint "R1206_N")
      (description "Resistor")
      (fields (field (name "PUBLISHER") "Altium Limited"))
      (libsource (lib "_ROBOT") (part "Resistor"))
    )
    (comp (ref "RsLedBP4")
      (value "1K")
      (footprint "R1206_N")
      (description "Resistor")
      (fields (field (name "PUBLISHER") "Altium Limited"))
      (libsource (lib "_ROBOT") (part "Resistor"))
    )
    (comp (ref "RsLedBP5")
      (value "1K")
      (footprint "R1206_N")
      (description "Resistor")
      (fields (field (name "PUBLISHER") "Altium Limited"))
      (libsource (lib "_ROBOT") (part "Resistor"))
    )
    (comp (ref "RsLedBPc")
      (value "1K")
      (footprint "R1206_N")
      (description "Resistor")
      (fields (field (name "PUBLISHER") "Altium Limited"))
      (libsource (lib "_ROBOT") (part "Resistor"))
    )
    (comp (ref "RsLedBPpm")
      (value "1K")
      (footprint "R1206_N")
      (description "Resistor")
      (fields (field (name "PUBLISHER") "Altium Limited"))
      (libsource (lib "_ROBOT") (part "Resistor"))
    )
    (comp (ref "RsLedBPrfu")
      (value "1K")
      (footprint "R1206_N")
      (description "Resistor")
      (fields (field (name "PUBLISHER") "Altium Limited"))
      (libsource (lib "_ROBOT") (part "Resistor"))
    )
    (comp (ref "RsLedBPst")
      (value "1K")
      (footprint "R1206_N")
      (description "Resistor")
      (fields (field (name "PUBLISHER") "Altium Limited"))
      (libsource (lib "_ROBOT") (part "Resistor"))
    )
    (comp (ref "Rsme12")
      (value "10k")
      (footprint "R1206_N")
      (description "Resistor")
      (fields (field (name "PUBLISHER") "Altium Limited"))
      (libsource (lib "_ROBOT") (part "Resistor"))
    )
    (comp (ref "Rsme24")
      (value "10k")
      (footprint "R1206_N")
      (description "Resistor")
      (fields (field (name "PUBLISHER") "Altium Limited"))
      (libsource (lib "_ROBOT") (part "Resistor"))
    )
    (comp (ref "Rsme24p")
      (value "10k")
      (footprint "R1206_N")
      (description "Resistor")
      (fields (field (name "PUBLISHER") "Altium Limited"))
      (libsource (lib "_ROBOT") (part "Resistor"))
    )
    (comp (ref "RsSW0")
      (value "1K")
      (footprint "R1206_N")
      (description "Resistor")
      (fields (field (name "PUBLISHER") "Altium Limited"))
      (libsource (lib "_ROBOT") (part "Resistor"))
    )
    (comp (ref "RsSW1")
      (value "1K")
      (footprint "R1206_N")
      (description "Resistor")
      (fields (field (name "PUBLISHER") "Altium Limited"))
      (libsource (lib "_ROBOT") (part "Resistor"))
    )
    (comp (ref "RsSW2")
      (value "1K")
      (footprint "R1206_N")
      (description "Resistor")
      (fields (field (name "PUBLISHER") "Altium Limited"))
      (libsource (lib "_ROBOT") (part "Resistor"))
    )
    (comp (ref "RsSW3")
      (value "1K")
      (footprint "R1206_N")
      (description "Resistor")
      (fields (field (name "PUBLISHER") "Altium Limited"))
      (libsource (lib "_ROBOT") (part "Resistor"))
    )
    (comp (ref "RsSW4")
      (value "1K")
      (footprint "R1206_N")
      (description "Resistor")
      (fields (field (name "PUBLISHER") "Altium Limited"))
      (libsource (lib "_ROBOT") (part "Resistor"))
    )
    (comp (ref "RsSW5")
      (value "1K")
      (footprint "R1206_N")
      (description "Resistor")
      (fields (field (name "PUBLISHER") "Altium Limited"))
      (libsource (lib "_ROBOT") (part "Resistor"))
    )
    (comp (ref "RsSW6")
      (value "1K")
      (footprint "R1206_N")
      (description "Resistor")
      (fields (field (name "PUBLISHER") "Altium Limited"))
      (libsource (lib "_ROBOT") (part "Resistor"))
    )
    (comp (ref "RsSW7")
      (value "1K")
      (footprint "R1206_N")
      (description "Resistor")
      (fields (field (name "PUBLISHER") "Altium Limited"))
      (libsource (lib "_ROBOT") (part "Resistor"))
    )
    (comp (ref "RsSW8")
      (value "1K")
      (footprint "R1206_N")
      (description "Resistor")
      (fields (field (name "PUBLISHER") "Altium Limited"))
      (libsource (lib "_ROBOT") (part "Resistor"))
    )
    (comp (ref "RsSW9")
      (value "1K")
      (footprint "R1206_N")
      (description "Resistor")
      (fields (field (name "PUBLISHER") "Altium Limited"))
      (libsource (lib "_ROBOT") (part "Resistor"))
    )
    (comp (ref "RsSW10")
      (value "1K")
      (footprint "R1206_N")
      (description "Resistor")
      (fields (field (name "PUBLISHER") "Altium Limited"))
      (libsource (lib "_ROBOT") (part "Resistor"))
    )
    (comp (ref "RsSW11")
      (value "1K")
      (footprint "R1206_N")
      (description "Resistor")
      (fields (field (name "PUBLISHER") "Altium Limited"))
      (libsource (lib "_ROBOT") (part "Resistor"))
    )
    (comp (ref "RsSW12")
      (value "1K")
      (footprint "R1206_N")
      (description "Resistor")
      (fields (field (name "PUBLISHER") "Altium Limited"))
      (libsource (lib "_ROBOT") (part "Resistor"))
    )
    (comp (ref "RsSW13")
      (value "1K")
      (footprint "R1206_N")
      (description "Resistor")
      (fields (field (name "PUBLISHER") "Altium Limited"))
      (libsource (lib "_ROBOT") (part "Resistor"))
    )
    (comp (ref "RsSW14")
      (value "1K")
      (footprint "R1206_N")
      (description "Resistor")
      (fields (field (name "PUBLISHER") "Altium Limited"))
      (libsource (lib "_ROBOT") (part "Resistor"))
    )
    (comp (ref "RsSW15")
      (value "1K")
      (footprint "R1206_N")
      (description "Resistor")
      (fields (field (name "PUBLISHER") "Altium Limited"))
      (libsource (lib "_ROBOT") (part "Resistor"))
    )
    (comp (ref "RsSW16")
      (value "1K")
      (footprint "R1206_N")
      (description "Resistor")
      (fields (field (name "PUBLISHER") "Altium Limited"))
      (libsource (lib "_ROBOT") (part "Resistor"))
    )
    (comp (ref "RsSW17")
      (value "1K")
      (footprint "R1206_N")
      (description "Resistor")
      (fields (field (name "PUBLISHER") "Altium Limited"))
      (libsource (lib "_ROBOT") (part "Resistor"))
    )
    (comp (ref "RsSW18")
      (value "1K")
      (footprint "R1206_N")
      (description "Resistor")
      (fields (field (name "PUBLISHER") "Altium Limited"))
      (libsource (lib "_ROBOT") (part "Resistor"))
    )
    (comp (ref "RsSWcolor")
      (value "1K")
      (footprint "R1206_N")
      (description "Resistor")
      (fields (field (name "PUBLISHER") "Altium Limited"))
      (libsource (lib "_ROBOT") (part "Resistor"))
    )
    (comp (ref "RsSWlcd")
      (value "1K")
      (footprint "R1206_N")
      (description "Resistor")
      (fields (field (name "PUBLISHER") "Altium Limited"))
      (libsource (lib "_ROBOT") (part "Resistor"))
    )
    (comp (ref "rx")
      (value "Goutte Strap_2")
      (footprint "Goutte Strap_2 Pads_Clearance 0.254mm")
      (fields (field (name "PUBLISHER") "Damien Guitton"))
      (libsource (lib "DG_Connecteur") (part "Goutte Strap_2"))
    )
    (comp (ref "R_ledRetro3")
      (value "~")
      (footprint "R1206_N")
      (description "Resistor")
      (fields (field (name "PUBLISHER") "Altium Limited"))
      (libsource (lib "_ROBOT") (part "Resistor"))
    )
    (comp (ref "R_ledRetro5")
      (value "~")
      (footprint "R1206_N")
      (description "Resistor")
      (fields (field (name "PUBLISHER") "Altium Limited"))
      (libsource (lib "_ROBOT") (part "Resistor"))
    )
    (comp (ref "STgnd")
      (value "Goutte Strap_2")
      (footprint "Goutte Strap_2 Pads_Clearance 0.254mm")
      (fields (field (name "PUBLISHER") "Damien Guitton"))
      (libsource (lib "DG_Connecteur") (part "Goutte Strap_2"))
    )
    (comp (ref "STM32")
      (value "STM32F407VGT6")
      (footprint "STM-LQFP100_N")
      (fields (field (name "MANUFACTURER") "STMicroelectronics"))
      (libsource (lib "STMicroelectronics STM32 F4") (part "STM32F407VGT6"))
    )
    (comp (ref "STR_CdCan1")
      (value "100nF")
      (footprint "C0805_N")
      (description "Capacitor")
      (fields (field (name "PUBLISHER") "Altium Limited"))
      (libsource (lib "_ROBOT") (part "Condensateur"))
    )
    (comp (ref "STR_CdCan2")
      (value "1µF")
      (footprint "C0805_N")
      (description "Capacitor")
      (fields (field (name "PUBLISHER") "Altium Limited"))
      (libsource (lib "_ROBOT") (part "Condensateur"))
    )
    (comp (ref "STR_Cu1rx")
      (value "100pF")
      (footprint "C0805_N")
      (description "Capacitor")
      (fields (field (name "PUBLISHER") "Altium Limited"))
      (libsource (lib "_ROBOT") (part "Condensateur"))
    )
    (comp (ref "STR_RdwnWAmI")
      (value "0")
      (footprint "R1206_N")
      (description "Resistor")
      (fields (field (name "PUBLISHER") "Altium Limited"))
      (libsource (lib "_ROBOT") (part "Resistor"))
    )
    (comp (ref "STR_RpuU1rx")
      (value "10k")
      (footprint "R1206_N")
      (description "Resistor")
      (fields (field (name "PUBLISHER") "Altium Limited"))
      (libsource (lib "_ROBOT") (part "Resistor"))
    )
    (comp (ref "STR_RpuU1tx")
      (value "1M")
      (footprint "R1206_N")
      (description "Resistor")
      (fields (field (name "PUBLISHER") "Altium Limited"))
      (libsource (lib "_ROBOT") (part "Resistor"))
    )
    (comp (ref "STR_Rsu1rx")
      (value "1k")
      (footprint "R1206_N")
      (description "Resistor")
      (fields (field (name "PUBLISHER") "Altium Limited"))
      (libsource (lib "_ROBOT") (part "Resistor"))
    )
    (comp (ref "STR_RsU1tx")
      (value "100")
      (footprint "R1206_N")
      (description "Resistor")
      (fields (field (name "PUBLISHER") "Altium Limited"))
      (libsource (lib "_ROBOT") (part "Resistor"))
    )
    (comp (ref "STR_RupWAmI")
      (value "0")
      (footprint "R1206_N")
      (description "Resistor")
      (fields (field (name "PUBLISHER") "Altium Limited"))
      (libsource (lib "_ROBOT") (part "Resistor"))
    )
    (comp (ref "STR_UART1")
      (value "RJ11_6/6")
      (footprint "RJ11_6/6 - Wurth Half Shielded Tab Down WR-MJ")
      (description "Right Angle, Standard Profile, Offset Latch DECconnect, Flangeless PCB Jack")
      (fields (field (name "PUBLISHER") "Altium Limited"))
      (libsource (lib "Connecteur") (part "RJ11_6/6"))
    )
    (comp (ref "STR_Ucan")
      (value "MCP2551-I/SN")
      (footprint "SO8_N")
      (description "High-Speed CAN Transceiver, 8-Pin SOIC, Industrial Temperature")
      (fields (field (name "PUBLISHER") "Damien Guitton"))
      (libsource (lib "Circuit intégré") (part "MCP2551-I/SN"))
    )
    (comp (ref "SW0")
      (value "25436NAH")
      (footprint "SW_UNIPOL_DROIT - Ebay - SPDT - 11x6x5")
      (description "Switch unipolaire a levier")
      (libsource (lib "_ROBOT") (part "SW SPDT- APEM Série 523x"))
    )
    (comp (ref "SW1")
      (value "25436NAH")
      (footprint "SW_UNIPOL_DROIT - Ebay - SPDT - 11x6x5")
      (description "Switch unipolaire a levier")
      (libsource (lib "_ROBOT") (part "SW SPDT- APEM Série 523x"))
    )
    (comp (ref "SW2")
      (value "25436NAH")
      (footprint "SW_UNIPOL_DROIT - Ebay - SPDT - 11x6x5")
      (description "Switch unipolaire a levier")
      (libsource (lib "_ROBOT") (part "SW SPDT- APEM Série 523x"))
    )
    (comp (ref "SW3")
      (value "25436NAH")
      (footprint "SW_UNIPOL_DROIT - Ebay - SPDT - 11x6x5")
      (description "Switch unipolaire a levier")
      (libsource (lib "_ROBOT") (part "SW SPDT- APEM Série 523x"))
    )
    (comp (ref "SW4")
      (value "25436NAH")
      (footprint "SW_UNIPOL_DROIT - Ebay - SPDT - 11x6x5")
      (description "Switch unipolaire a levier")
      (libsource (lib "_ROBOT") (part "SW SPDT- APEM Série 523x"))
    )
    (comp (ref "SW5")
      (value "25436NAH")
      (footprint "SW_UNIPOL_DROIT - Ebay - SPDT - 11x6x5")
      (description "Switch unipolaire a levier")
      (libsource (lib "_ROBOT") (part "SW SPDT- APEM Série 523x"))
    )
    (comp (ref "SW6")
      (value "25436NAH")
      (footprint "SW_UNIPOL_DROIT - Ebay - SPDT - 11x6x5")
      (description "Switch unipolaire a levier")
      (libsource (lib "_ROBOT") (part "SW SPDT- APEM Série 523x"))
    )
    (comp (ref "SW7")
      (value "25436NAH")
      (footprint "SW_UNIPOL_DROIT - Ebay - SPDT - 11x6x5")
      (description "Switch unipolaire a levier")
      (libsource (lib "_ROBOT") (part "SW SPDT- APEM Série 523x"))
    )
    (comp (ref "SW8")
      (value "25436NAH")
      (footprint "SW_UNIPOL_DROIT - Ebay - SPDT - 11x6x5")
      (description "Switch unipolaire a levier")
      (libsource (lib "_ROBOT") (part "SW SPDT- APEM Série 523x"))
    )
    (comp (ref "SW9")
      (value "25436NAH")
      (footprint "SW_UNIPOL_DROIT - Ebay - SPDT - 11x6x5")
      (description "Switch unipolaire a levier")
      (libsource (lib "_ROBOT") (part "SW SPDT- APEM Série 523x"))
    )
    (comp (ref "SW10")
      (value "25436NAH")
      (footprint "SW_UNIPOL_DROIT - Ebay - SPDT - 11x6x5")
      (description "Switch unipolaire a levier")
      (libsource (lib "_ROBOT") (part "SW SPDT- APEM Série 523x"))
    )
    (comp (ref "SW11")
      (value "25436NAH")
      (footprint "SW_UNIPOL_DROIT - Ebay - SPDT - 11x6x5")
      (description "Switch unipolaire a levier")
      (libsource (lib "_ROBOT") (part "SW SPDT- APEM Série 523x"))
    )
    (comp (ref "SW12")
      (value "25436NAH")
      (footprint "SW_UNIPOL_DROIT - Ebay - SPDT - 11x6x5")
      (description "Switch unipolaire a levier")
      (libsource (lib "_ROBOT") (part "SW SPDT- APEM Série 523x"))
    )
    (comp (ref "SW13")
      (value "25436NAH")
      (footprint "SW_UNIPOL_DROIT - Ebay - SPDT - 11x6x5")
      (description "Switch unipolaire a levier")
      (libsource (lib "_ROBOT") (part "SW SPDT- APEM Série 523x"))
    )
    (comp (ref "SW14")
      (value "25436NAH")
      (footprint "SW_UNIPOL_DROIT - Ebay - SPDT - 11x6x5")
      (description "Switch unipolaire a levier")
      (libsource (lib "_ROBOT") (part "SW SPDT- APEM Série 523x"))
    )
    (comp (ref "SW15")
      (value "25436NAH")
      (footprint "SW_UNIPOL_DROIT - Ebay - SPDT - 11x6x5")
      (description "Switch unipolaire a levier")
      (libsource (lib "_ROBOT") (part "SW SPDT- APEM Série 523x"))
    )
    (comp (ref "SW16")
      (value "25436NAH")
      (footprint "SW_UNIPOL_DROIT - Ebay - SPDT - 11x6x5")
      (description "Switch unipolaire a levier")
      (libsource (lib "_ROBOT") (part "SW SPDT- APEM Série 523x"))
    )
    (comp (ref "SW17")
      (value "25436NAH")
      (footprint "SW_UNIPOL_DROIT - Ebay - SPDT - 11x6x5")
      (description "Switch unipolaire a levier")
      (libsource (lib "_ROBOT") (part "SW SPDT- APEM Série 523x"))
    )
    (comp (ref "SW18")
      (value "25436NAH")
      (footprint "SW_UNIPOL_DROIT - Ebay - SPDT - 11x6x5")
      (description "Switch unipolaire a levier")
      (libsource (lib "_ROBOT") (part "SW SPDT- APEM Série 523x"))
    )
    (comp (ref "SWcolor")
      (value "25436NAH")
      (footprint "SW_UNIPOL_DROIT - APEM 18235")
      (description "Switch unipolaire a levier")
      (libsource (lib "_ROBOT") (part "SW SPDT- APEM Série 523x"))
    )
    (comp (ref "SWlcd")
      (value "25436NAH")
      (footprint "SW_UNIPOL_DROIT - Ebay - SPDT - 11x6x5")
      (description "Switch unipolaire a levier")
      (libsource (lib "_ROBOT") (part "SW SPDT- APEM Série 523x"))
    )
    (comp (ref "TR_5V")
      (value "TRACO THN 20-4811Wi")
      (footprint "TRACO_THN20")
      (description "Traco 20W 24V to 5V*4A")
      (fields (field (name "REF") "THN 20-4811Wi"))
      (libsource (lib "_ROBOT") (part "TRACO THN 20-4811Wi"))
    )
    (comp (ref "tx")
      (value "Goutte Strap_2")
      (footprint "Goutte Strap_2 Pads_Clearance 0.254mm")
      (fields (field (name "PUBLISHER") "Damien Guitton"))
      (libsource (lib "DG_Connecteur") (part "Goutte Strap_2"))
    )
    (comp (ref "Ureg_3V")
      (value "MCP1826S-3302E/DB")
      (footprint "SOT223-4N")
      (description "1000 mA, Low Voltage, Low Quiescent Current LDO Regulator, 3-Pin SOT-223, Extended Temperature")
      (fields (field (name "PUBLISHER") "Altium Limited"))
      (libsource (lib "Microchip Power Mgt Line Regulator") (part "MCP1826S-3302E/DB"))
    )
    (comp (ref "V1")
      (value "Pad_M3")
      (footprint "M3x6mm")
      (description "Vis M3 X 6mm _TORX_Tête 6mm")
      (fields (field (name "PUBLISHER") "Damien Guitton"))
      (libsource (lib "_ROBOT") (part "Vis M3 X 6mm _TORX_Tête 6mm"))
    )
    (comp (ref "V2")
      (value "Pad_M3")
      (footprint "M3x6mm")
      (description "Vis M3 X 6mm _TORX_Tête 6mm")
      (fields (field (name "PUBLISHER") "Damien Guitton"))
      (libsource (lib "_ROBOT") (part "Vis M3 X 6mm _TORX_Tête 6mm"))
    )
    (comp (ref "V3")
      (value "Pad_M3")
      (footprint "M3x6mm")
      (description "Vis M3 X 6mm _TORX_Tête 6mm")
      (fields (field (name "PUBLISHER") "Damien Guitton"))
      (libsource (lib "_ROBOT") (part "Vis M3 X 6mm _TORX_Tête 6mm"))
    )
    (comp (ref "V4")
      (value "Pad_M3")
      (footprint "M3x6mm")
      (description "Vis M3 X 6mm _TORX_Tête 6mm")
      (fields (field (name "PUBLISHER") "Damien Guitton"))
      (libsource (lib "_ROBOT") (part "Vis M3 X 6mm _TORX_Tête 6mm"))
    )
    (comp (ref "V5")
      (value "Pad_M3")
      (footprint "M3x6mm")
      (description "Vis M3 X 6mm _TORX_Tête 6mm")
      (fields (field (name "PUBLISHER") "Damien Guitton"))
      (libsource (lib "_ROBOT") (part "Vis M3 X 6mm _TORX_Tête 6mm"))
    )
    (comp (ref "V6")
      (value "Pad_M3")
      (footprint "M3x6mm")
      (description "Vis M3 X 6mm _TORX_Tête 6mm")
      (fields (field (name "PUBLISHER") "Damien Guitton"))
      (libsource (lib "_ROBOT") (part "Vis M3 X 6mm _TORX_Tête 6mm"))
    )
    (comp (ref "V7")
      (value "Pad_M3")
      (footprint "M3x6mm")
      (description "Vis M3 X 6mm _TORX_Tête 6mm")
      (fields (field (name "PUBLISHER") "Damien Guitton"))
      (libsource (lib "_ROBOT") (part "Vis M3 X 6mm _TORX_Tête 6mm"))
    )
    (comp (ref "V8")
      (value "Pad_M3")
      (footprint "M3x6mm")
      (description "Vis M3 X 6mm _TORX_Tête 6mm")
      (fields (field (name "PUBLISHER") "Damien Guitton"))
      (libsource (lib "_ROBOT") (part "Vis M3 X 6mm _TORX_Tête 6mm"))
    )
    (comp (ref "V9")
      (value "Pad_M3")
      (footprint "M3x6mm")
      (description "Vis M3 X 6mm _TORX_Tête 6mm")
      (fields (field (name "PUBLISHER") "Damien Guitton"))
      (libsource (lib "_ROBOT") (part "Vis M3 X 6mm _TORX_Tête 6mm"))
    )
    (comp (ref "Y1")
      (value "8 MHz")
      (footprint "HC49/4H_SMX")
      (description "Crystal Oscillator")
      (fields (field (name "PUBLISHER") "Altium Limited"))
      (libsource (lib "_ROBOT") (part "Quartz"))
    )
    (comp (ref "YAHOURT")
      (value "BARRETTE_8 CONTACTS_2 RANGEES_MALE_DROITE")
      (footprint "HE10/16_M_D_B P")
      (fields (field (name "TYPE") "M_D_8X2"))
      (libsource (lib "connecteurs") (part "BARRETTE_8 CONTACTS_2 RANGEES_MALE_DROITE"))
    )
  )
  (nets
    (net (code "1") (name "/CANH") (class "Default")
      (node (ref "FdP") (pin "15") (pinfunction "15_15") (pintype "passive"))
      (node (ref "STR_Ucan") (pin "7") (pinfunction "CANH_7") (pintype "bidirectional"))
      (node (ref "YAHOURT") (pin "15") (pinfunction "15_15") (pintype "passive"))
    )
    (net (code "2") (name "/CANL") (class "Default")
      (node (ref "FdP") (pin "16") (pinfunction "16_16") (pintype "passive"))
      (node (ref "STR_Ucan") (pin "6") (pinfunction "CANL_6") (pintype "bidirectional"))
      (node (ref "YAHOURT") (pin "16") (pinfunction "16_16") (pintype "passive"))
    )
    (net (code "3") (name "/IHM_I_AM_READY") (class "Default")
      (node (ref "FdP") (pin "3") (pinfunction "3_3") (pintype "passive"))
      (node (ref "Rihm_ready") (pin "1") (pinfunction "1_1") (pintype "passive"))
    )
    (net (code "4") (name "/PA0_BP_Selftest") (class "Default")
      (node (ref "CfBPst") (pin "2") (pinfunction "2_2") (pintype "passive"))
      (node (ref "RsBPst") (pin "2") (pinfunction "2_2") (pintype "passive"))
      (node (ref "STM32") (pin "23") (pinfunction "PA0-WKUP(PA0)_23") (pintype "bidirectional"))
    )
    (net (code "5") (name "/PA1_BP_CALIBRATION") (class "Default")
      (node (ref "CfBPc") (pin "2") (pinfunction "2_2") (pintype "passive"))
      (node (ref "RsBPc") (pin "2") (pinfunction "2_2") (pintype "passive"))
      (node (ref "STM32") (pin "24") (pinfunction "PA1_24") (pintype "bidirectional"))
    )
    (net (code "6") (name "/PA3_BP_Print_Match") (class "Default")
      (node (ref "CfBPpm") (pin "2") (pinfunction "2_2") (pintype "passive"))
      (node (ref "RsBPpm") (pin "2") (pinfunction "2_2") (pintype "passive"))
      (node (ref "STM32") (pin "26") (pinfunction "PA3_26") (pintype "bidirectional"))
    )
    (net (code "7") (name "/PA4_BP0") (class "Default")
      (node (ref "CfBP0") (pin "2") (pinfunction "2_2") (pintype "passive"))
      (node (ref "RsBP0") (pin "2") (pinfunction "2_2") (pintype "passive"))
      (node (ref "STM32") (pin "29") (pinfunction "PA4_29") (pintype "bidirectional"))
    )
    (net (code "8") (name "/PA5_Meas_12Vhok") (class "Default")
      (node (ref "Cmes12") (pin "2") (pinfunction "2_2") (pintype "passive"))
      (node (ref "Rsme12") (pin "2") (pinfunction "2_2") (pintype "passive"))
      (node (ref "STM32") (pin "30") (pinfunction "PA5_30") (pintype "bidirectional"))
    )
    (net (code "9") (name "/PA6_Meas_24Vpsce") (class "Default")
      (node (ref "Cmes24p") (pin "2") (pinfunction "2_2") (pintype "passive"))
      (node (ref "Rsme24p") (pin "2") (pinfunction "2_2") (pintype "passive"))
      (node (ref "STM32") (pin "31") (pinfunction "PA6_31") (pintype "bidirectional"))
    )
    (net (code "10") (name "/PA7_BP1") (class "Default")
      (node (ref "CfBP1") (pin "2") (pinfunction "2_2") (pintype "passive"))
      (node (ref "RsBP1") (pin "2") (pinfunction "2_2") (pintype "passive"))
      (node (ref "STM32") (pin "32") (pinfunction "PA7_32") (pintype "bidirectional"))
    )
    (net (code "11") (name "/PA9_BP2") (class "Default")
      (node (ref "CfBP2") (pin "2") (pinfunction "2_2") (pintype "passive"))
      (node (ref "RsBP2") (pin "2") (pinfunction "2_2") (pintype "passive"))
      (node (ref "STM32") (pin "68") (pinfunction "PA9_68") (pintype "bidirectional"))
    )
    (net (code "12") (name "/PA10_BP3") (class "Default")
      (node (ref "CfBP3") (pin "2") (pinfunction "2_2") (pintype "passive"))
      (node (ref "RsBP3") (pin "2") (pinfunction "2_2") (pintype "passive"))
      (node (ref "STM32") (pin "69") (pinfunction "PA10_69") (pintype "bidirectional"))
    )
    (net (code "13") (name "/PA11_BP4") (class "Default")
      (node (ref "CfBP4") (pin "2") (pinfunction "2_2") (pintype "passive"))
      (node (ref "RsBP4") (pin "2") (pinfunction "2_2") (pintype "passive"))
      (node (ref "STM32") (pin "70") (pinfunction "PA11_70") (pintype "bidirectional"))
    )
    (net (code "14") (name "/PA12_BP5") (class "Default")
      (node (ref "CfBP5") (pin "2") (pinfunction "2_2") (pintype "passive"))
      (node (ref "RsBP5") (pin "2") (pinfunction "2_2") (pintype "passive"))
      (node (ref "STM32") (pin "71") (pinfunction "PA12_71") (pintype "bidirectional"))
    )
    (net (code "15") (name "/PB0_SW_LCD") (class "Default")
      (node (ref "CfSWlcd") (pin "2") (pinfunction "2_2") (pintype "passive"))
      (node (ref "RsSWlcd") (pin "2") (pinfunction "2_2") (pintype "passive"))
      (node (ref "STM32") (pin "35") (pinfunction "PB0_35") (pintype "bidirectional"))
    )
    (net (code "16") (name "/PB1_BP_OK") (class "Default")
      (node (ref "STM32") (pin "36") (pinfunction "PB1_36") (pintype "bidirectional"))
    )
    (net (code "17") (name "/PB2_BP_+") (class "Default")
      (node (ref "STM32") (pin "37") (pinfunction "PB2-BOOT1(PB2)_37") (pintype "bidirectional"))
    )
    (net (code "18") (name "/PB4_PB_-") (class "Default")
      (node (ref "STM32") (pin "90") (pinfunction "PB4(NJTRST)_90") (pintype "bidirectional"))
    )
    (net (code "19") (name "/PB5_BP_Set") (class "Default")
      (node (ref "STM32") (pin "91") (pinfunction "PB5_91") (pintype "bidirectional"))
    )
    (net (code "20") (name "/PB6_U1TX") (class "Default")
      (node (ref "STM32") (pin "92") (pinfunction "PB6_92") (pintype "bidirectional"))
      (node (ref "STR_RsU1tx") (pin "2") (pinfunction "2_2") (pintype "passive"))
    )
    (net (code "21") (name "/PB7_U1RX") (class "Default")
      (node (ref "STM32") (pin "93") (pinfunction "PB7_93") (pintype "bidirectional"))
      (node (ref "STR_Cu1rx") (pin "2") (pinfunction "2_2") (pintype "passive"))
      (node (ref "STR_RpuU1rx") (pin "1") (pinfunction "1_1") (pintype "passive"))
      (node (ref "STR_Rsu1rx") (pin "1") (pinfunction "1_1") (pintype "passive"))
    )
    (net (code "22") (name "/PB8_I_AM_READY") (class "Default")
      (node (ref "Rihm_ready") (pin "2") (pinfunction "2_2") (pintype "passive"))
      (node (ref "STM32") (pin "95") (pinfunction "PB8_95") (pintype "bidirectional"))
    )
    (net (code "23") (name "/PB9_LCD_Reset") (class "Default")
      (node (ref "*") (pin "4") (pinfunction "RESET_4") (pintype "passive"))
      (node (ref "STM32") (pin "96") (pinfunction "PB9_96") (pintype "bidirectional"))
    )
    (net (code "24") (name "/PB10_LCD_SCL") (class "Default")
      (node (ref "STM32") (pin "47") (pinfunction "PB10_47") (pintype "bidirectional"))
    )
    (net (code "25") (name "/PB11_LCD_SDA") (class "Default")
      (node (ref "STM32") (pin "48") (pinfunction "PB11_48") (pintype "bidirectional"))
    )
    (net (code "26") (name "/PB12_SPI_CS") (class "Default")
      (node (ref "*") (pin "3") (pinfunction "CS_3") (pintype "passive"))
      (node (ref "STM32") (pin "51") (pinfunction "PB12_51") (pintype "bidirectional"))
    )
    (net (code "27") (name "/PB13_SPI_SCK") (class "Default")
      (node (ref "*") (pin "10") (pinfunction "T_CLK_10") (pintype "passive"))
      (node (ref "*") (pin "7") (pinfunction "SCK_7") (pintype "passive"))
      (node (ref "STM32") (pin "52") (pinfunction "PB13_52") (pintype "bidirectional"))
    )
    (net (code "28") (name "/PB14_SPI_MISO") (class "Default")
      (node (ref "*") (pin "13") (pinfunction "T_DOUT_13") (pintype "passive"))
      (node (ref "*") (pin "9") (pinfunction "MISO_9") (pintype "passive"))
      (node (ref "STM32") (pin "53") (pinfunction "PB14_53") (pintype "bidirectional"))
    )
    (net (code "29") (name "/PB15_SPI_MOSI") (class "Default")
      (node (ref "*") (pin "12") (pinfunction "T_DIN_12") (pintype "passive"))
      (node (ref "*") (pin "6") (pinfunction "MOSI_6") (pintype "passive"))
      (node (ref "STM32") (pin "54") (pinfunction "PB15_54") (pintype "bidirectional"))
    )
    (net (code "30") (name "/PC0_Meas_24Vperm") (class "Default")
      (node (ref "Cmes24") (pin "2") (pinfunction "2_2") (pintype "passive"))
      (node (ref "Rsme24") (pin "2") (pinfunction "2_2") (pintype "passive"))
      (node (ref "STM32") (pin "15") (pinfunction "PC0_15") (pintype "bidirectional"))
    )
    (net (code "31") (name "/PC1_SW16") (class "Default")
      (node (ref "CfSW16") (pin "2") (pinfunction "2_2") (pintype "passive"))
      (node (ref "RsSW16") (pin "2") (pinfunction "2_2") (pintype "passive"))
      (node (ref "STM32") (pin "16") (pinfunction "PC1_16") (pintype "bidirectional"))
    )
    (net (code "32") (name "/PC2_SW17") (class "Default")
      (node (ref "CfSW17") (pin "2") (pinfunction "2_2") (pintype "passive"))
      (node (ref "RsSW17") (pin "2") (pinfunction "2_2") (pintype "passive"))
      (node (ref "STM32") (pin "17") (pinfunction "PC2_17") (pintype "bidirectional"))
    )
    (net (code "33") (name "/PC3_SW18") (class "Default")
      (node (ref "CfSW18") (pin "2") (pinfunction "2_2") (pintype "passive"))
      (node (ref "RsSW18") (pin "2") (pinfunction "2_2") (pintype "passive"))
      (node (ref "STM32") (pin "18") (pinfunction "PC3_18") (pintype "bidirectional"))
    )
    (net (code "34") (name "/PC4_BP_RFU") (class "Default")
      (node (ref "CfBPrfu") (pin "2") (pinfunction "2_2") (pintype "passive"))
      (node (ref "RsBPrfu") (pin "2") (pinfunction "2_2") (pintype "passive"))
      (node (ref "STM32") (pin "33") (pinfunction "PC4_33") (pintype "bidirectional"))
    )
    (net (code "35") (name "/PC5_SW2") (class "Default")
      (node (ref "CfSW2") (pin "2") (pinfunction "2_2") (pintype "passive"))
      (node (ref "RsSW2") (pin "2") (pinfunction "2_2") (pintype "passive"))
      (node (ref "STM32") (pin "34") (pinfunction "PC5_34") (pintype "bidirectional"))
    )
    (net (code "36") (name "/PC6_LED_OK") (class "Default")
      (node (ref "STM32") (pin "63") (pinfunction "PC6_63") (pintype "bidirectional"))
    )
    (net (code "37") (name "/PC7_LED_Set") (class "Default")
      (node (ref "STM32") (pin "64") (pinfunction "PC7_64") (pintype "bidirectional"))
    )
    (net (code "38") (name "/PC8_LED_+") (class "Default")
      (node (ref "STM32") (pin "65") (pinfunction "PC8_65") (pintype "bidirectional"))
    )
    (net (code "39") (name "/PC9_LED_-") (class "Default")
      (node (ref "STM32") (pin "66") (pinfunction "PC9_66") (pintype "bidirectional"))
    )
    (net (code "40") (name "/PC10_T_CS") (class "Default")
      (node (ref "*") (pin "11") (pinfunction "T_CS_11") (pintype "passive"))
      (node (ref "STM32") (pin "78") (pinfunction "PC10_78") (pintype "bidirectional"))
    )
    (net (code "41") (name "/PC11_DC") (class "Default")
      (node (ref "*") (pin "5") (pinfunction "D/C_5") (pintype "passive"))
      (node (ref "STM32") (pin "79") (pinfunction "PC11_79") (pintype "bidirectional"))
    )
    (net (code "42") (name "/PC13_WHO_AM_I") (class "Default")
      (node (ref "STM32") (pin "7") (pinfunction "PC13_7") (pintype "bidirectional"))
      (node (ref "STR_RdwnWAmI") (pin "2") (pinfunction "2_2") (pintype "passive"))
      (node (ref "STR_RupWAmI") (pin "1") (pinfunction "1_1") (pintype "passive"))
    )
    (net (code "43") (name "/PD0_CANRX") (class "Default")
      (node (ref "STM32") (pin "81") (pinfunction "PD0_81") (pintype "bidirectional"))
      (node (ref "STR_Ucan") (pin "4") (pinfunction "RXD_4") (pintype "output"))
    )
    (net (code "44") (name "/PD1_CANTX") (class "Default")
      (node (ref "STM32") (pin "82") (pinfunction "PD1_82") (pintype "bidirectional"))
      (node (ref "STR_Ucan") (pin "1") (pinfunction "TXD_1") (pintype "input"))
    )
    (net (code "45") (name "/PD2_LED_Green") (class "Default")
      (node (ref "RGreen") (pin "1") (pinfunction "1_1") (pintype "passive"))
      (node (ref "STM32") (pin "83") (pinfunction "PD2_83") (pintype "bidirectional"))
    )
    (net (code "46") (name "/PD3_LED_Red") (class "Default")
      (node (ref "Rred") (pin "1") (pinfunction "1_1") (pintype "passive"))
      (node (ref "STM32") (pin "84") (pinfunction "PD3_84") (pintype "bidirectional"))
    )
    (net (code "47") (name "/PD4_LED_Blue") (class "Default")
      (node (ref "RBlue") (pin "1") (pinfunction "1_1") (pintype "passive"))
      (node (ref "STM32") (pin "85") (pinfunction "PD4_85") (pintype "bidirectional"))
    )
    (net (code "48") (name "/PD5_T_IRQ") (class "Default")
      (node (ref "*") (pin "14") (pinfunction "T_IRQ_14") (pintype "passive"))
      (node (ref "STM32") (pin "86") (pinfunction "PD5_86") (pintype "bidirectional"))
    )
    (net (code "49") (name "/PD6_SW_Color") (class "Default")
      (node (ref "CfSWcolor") (pin "2") (pinfunction "2_2") (pintype "passive"))
      (node (ref "RsSWcolor") (pin "2") (pinfunction "2_2") (pintype "passive"))
      (node (ref "STM32") (pin "87") (pinfunction "PD6_87") (pintype "bidirectional"))
    )
    (net (code "50") (name "/PD7_Biroute") (class "Default")
      (node (ref "CfBir") (pin "2") (pinfunction "2_2") (pintype "passive"))
      (node (ref "RsBir") (pin "2") (pinfunction "2_2") (pintype "passive"))
      (node (ref "STM32") (pin "88") (pinfunction "PD7_88") (pintype "bidirectional"))
    )
    (net (code "51") (name "/PD10_LED0") (class "Default")
      (node (ref "LEDs") (pin "6") (pinfunction "6_6") (pintype "passive"))
      (node (ref "Rled0") (pin "2") (pinfunction "2_2") (pintype "passive"))
      (node (ref "STM32") (pin "57") (pinfunction "PD10_57") (pintype "bidirectional"))
    )
    (net (code "52") (name "/PD11_LED1") (class "Default")
      (node (ref "Rled1") (pin "2") (pinfunction "2_2") (pintype "passive"))
      (node (ref "STM32") (pin "58") (pinfunction "PD11_58") (pintype "bidirectional"))
    )
    (net (code "53") (name "/PD12_LED2") (class "Default")
      (node (ref "LEDs") (pin "3") (pinfunction "3_3") (pintype "passive"))
      (node (ref "Rled2") (pin "2") (pinfunction "2_2") (pintype "passive"))
      (node (ref "STM32") (pin "59") (pinfunction "PD12_59") (pintype "bidirectional"))
    )
    (net (code "54") (name "/PD13_LED3") (class "Default")
      (node (ref "LEDs") (pin "5") (pinfunction "5_5") (pintype "passive"))
      (node (ref "Rled3") (pin "2") (pinfunction "2_2") (pintype "passive"))
      (node (ref "STM32") (pin "60") (pinfunction "PD13_60") (pintype "bidirectional"))
    )
    (net (code "55") (name "/PD14_LED4") (class "Default")
      (node (ref "Rled4") (pin "2") (pinfunction "2_2") (pintype "passive"))
      (node (ref "STM32") (pin "61") (pinfunction "PD14_61") (pintype "bidirectional"))
    )
    (net (code "56") (name "/PD15_LED5") (class "Default")
      (node (ref "LEDs") (pin "4") (pinfunction "4_4") (pintype "passive"))
      (node (ref "Rled5") (pin "2") (pinfunction "2_2") (pintype "passive"))
      (node (ref "STM32") (pin "62") (pinfunction "PD15_62") (pintype "bidirectional"))
    )
    (net (code "57") (name "/PE0_SW0") (class "Default")
      (node (ref "CfSW0") (pin "2") (pinfunction "2_2") (pintype "passive"))
      (node (ref "RsSW0") (pin "2") (pinfunction "2_2") (pintype "passive"))
      (node (ref "STM32") (pin "97") (pinfunction "PE0_97") (pintype "bidirectional"))
    )
    (net (code "58") (name "/PE1_SW1") (class "Default")
      (node (ref "CfSW1") (pin "2") (pinfunction "2_2") (pintype "passive"))
      (node (ref "RsSW1") (pin "2") (pinfunction "2_2") (pintype "passive"))
      (node (ref "STM32") (pin "98") (pinfunction "PE1_98") (pintype "bidirectional"))
    )
    (net (code "59") (name "/PE3_SW3") (class "Default")
      (node (ref "CfSW3") (pin "2") (pinfunction "2_2") (pintype "passive"))
      (node (ref "RsSW3") (pin "2") (pinfunction "2_2") (pintype "passive"))
      (node (ref "STM32") (pin "2") (pinfunction "PE3_2") (pintype "bidirectional"))
    )
    (net (code "60") (name "/PE4_SW4") (class "Default")
      (node (ref "CfSW4") (pin "2") (pinfunction "2_2") (pintype "passive"))
      (node (ref "RsSW4") (pin "2") (pinfunction "2_2") (pintype "passive"))
      (node (ref "STM32") (pin "3") (pinfunction "PE4_3") (pintype "bidirectional"))
    )
    (net (code "61") (name "/PE5_SW5") (class "Default")
      (node (ref "CfSW5") (pin "2") (pinfunction "2_2") (pintype "passive"))
      (node (ref "RsSW5") (pin "2") (pinfunction "2_2") (pintype "passive"))
      (node (ref "STM32") (pin "4") (pinfunction "PE5_4") (pintype "bidirectional"))
    )
    (net (code "62") (name "/PE6_SW6") (class "Default")
      (node (ref "CfSW6") (pin "2") (pinfunction "2_2") (pintype "passive"))
      (node (ref "RsSW6") (pin "2") (pinfunction "2_2") (pintype "passive"))
      (node (ref "STM32") (pin "5") (pinfunction "PE6_5") (pintype "bidirectional"))
    )
    (net (code "63") (name "/PE7_SW7") (class "Default")
      (node (ref "CfSW7") (pin "2") (pinfunction "2_2") (pintype "passive"))
      (node (ref "RsSW7") (pin "2") (pinfunction "2_2") (pintype "passive"))
      (node (ref "STM32") (pin "38") (pinfunction "PE7_38") (pintype "bidirectional"))
    )
    (net (code "64") (name "/PE8_SW8") (class "Default")
      (node (ref "CfSW8") (pin "2") (pinfunction "2_2") (pintype "passive"))
      (node (ref "RsSW8") (pin "2") (pinfunction "2_2") (pintype "passive"))
      (node (ref "STM32") (pin "39") (pinfunction "PE8_39") (pintype "bidirectional"))
    )
    (net (code "65") (name "/PE9_SW9") (class "Default")
      (node (ref "CfSW9") (pin "2") (pinfunction "2_2") (pintype "passive"))
      (node (ref "RsSW9") (pin "2") (pinfunction "2_2") (pintype "passive"))
      (node (ref "STM32") (pin "40") (pinfunction "PE9_40") (pintype "bidirectional"))
    )
    (net (code "66") (name "/PE10_SW10") (class "Default")
      (node (ref "CfSW10") (pin "2") (pinfunction "2_2") (pintype "passive"))
      (node (ref "RsSW10") (pin "2") (pinfunction "2_2") (pintype "passive"))
      (node (ref "STM32") (pin "41") (pinfunction "PE10_41") (pintype "bidirectional"))
    )
    (net (code "67") (name "/PE11_SW11") (class "Default")
      (node (ref "CfSW11") (pin "2") (pinfunction "2_2") (pintype "passive"))
      (node (ref "RsSW11") (pin "2") (pinfunction "2_2") (pintype "passive"))
      (node (ref "STM32") (pin "42") (pinfunction "PE11_42") (pintype "bidirectional"))
    )
    (net (code "68") (name "/PE12_SW12") (class "Default")
      (node (ref "CfSW12") (pin "2") (pinfunction "2_2") (pintype "passive"))
      (node (ref "RsSW12") (pin "2") (pinfunction "2_2") (pintype "passive"))
      (node (ref "STM32") (pin "43") (pinfunction "PE12_43") (pintype "bidirectional"))
    )
    (net (code "69") (name "/PE13_SW13") (class "Default")
      (node (ref "CfSW13") (pin "2") (pinfunction "2_2") (pintype "passive"))
      (node (ref "RsSW13") (pin "2") (pinfunction "2_2") (pintype "passive"))
      (node (ref "STM32") (pin "44") (pinfunction "PE13_44") (pintype "bidirectional"))
    )
    (net (code "70") (name "/PE14_SW14") (class "Default")
      (node (ref "CfSW14") (pin "2") (pinfunction "2_2") (pintype "passive"))
      (node (ref "RsSW14") (pin "2") (pinfunction "2_2") (pintype "passive"))
      (node (ref "STM32") (pin "45") (pinfunction "PE14_45") (pintype "bidirectional"))
    )
    (net (code "71") (name "/PE15_SW15") (class "Default")
      (node (ref "CfSW15") (pin "2") (pinfunction "2_2") (pintype "passive"))
      (node (ref "RsSW15") (pin "2") (pinfunction "2_2") (pintype "passive"))
      (node (ref "STM32") (pin "46") (pinfunction "PE15_46") (pintype "bidirectional"))
    )
    (net (code "72") (name "/PROG_NRST") (class "Default")
      (node (ref "Cnrst") (pin "2") (pinfunction "2_2") (pintype "passive"))
      (node (ref "P1") (pin "5") (pinfunction "NRST_5") (pintype "passive"))
      (node (ref "Rnrst") (pin "1") (pinfunction "1_1") (pintype "passive"))
      (node (ref "STM32") (pin "14") (pinfunction "NRST_14") (pintype "bidirectional"))
    )
    (net (code "73") (name "/PROG_SWCLK") (class "Default")
      (node (ref "P1") (pin "2") (pinfunction "SWCLK_2") (pintype "passive"))
      (node (ref "STM32") (pin "76") (pinfunction "PA14(JTCK-SWCLK)_76") (pintype "bidirectional"))
    )
    (net (code "74") (name "/PROG_SWDIO") (class "Default")
      (node (ref "P1") (pin "4") (pinfunction "SWDIO_4") (pintype "passive"))
      (node (ref "STM32") (pin "72") (pinfunction "PA13(JTMS-SWDIO)_72") (pintype "bidirectional"))
    )
    (net (code "75") (name "/PROG_SWO") (class "Default")
      (node (ref "P1") (pin "6") (pinfunction "SWO_6") (pintype "passive"))
      (node (ref "STM32") (pin "89") (pinfunction "PB3(JTDO/TRACESWO)_89") (pintype "bidirectional"))
    )
    (net (code "76") (name "/STR_LCD_SCL") (class "Default")
      (node (ref "FdP") (pin "14") (pinfunction "14_14") (pintype "passive"))
    )
    (net (code "77") (name "/STR_LCD_SDA") (class "Default")
      (node (ref "FdP") (pin "7") (pinfunction "7_7") (pintype "passive"))
    )
    (net (code "78") (name "/STR_PA2_XBEE_TX") (class "Default")
      (node (ref "FdP") (pin "5") (pinfunction "5_5") (pintype "passive"))
      (node (ref "YAHOURT") (pin "5") (pinfunction "5_5") (pintype "passive"))
    )
    (net (code "79") (name "/STR_PA3_XBEE_RX") (class "Default")
      (node (ref "FdP") (pin "6") (pinfunction "6_6") (pintype "passive"))
      (node (ref "YAHOURT") (pin "6") (pinfunction "6_6") (pintype "passive"))
    )
    (net (code "80") (name "/STR_PA5_RF_XBEE_RESET") (class "Default")
      (node (ref "FdP") (pin "10") (pinfunction "10_10") (pintype "passive"))
      (node (ref "FdP") (pin "8") (pinfunction "8_8") (pintype "passive"))
      (node (ref "YAHOURT") (pin "10") (pinfunction "10_10") (pintype "passive"))
      (node (ref "YAHOURT") (pin "8") (pinfunction "8_8") (pintype "passive"))
    )
    (net (code "81") (name "/STR_PA6_RF_Config") (class "Default")
      (node (ref "FdP") (pin "11") (pinfunction "11_11") (pintype "passive"))
      (node (ref "YAHOURT") (pin "11") (pinfunction "11_11") (pintype "passive"))
    )
    (net (code "82") (name "/STR_PC8_SynchroBalise") (class "Default")
      (node (ref "FdP") (pin "13") (pinfunction "13_13") (pintype "passive"))
      (node (ref "YAHOURT") (pin "13") (pinfunction "13_13") (pintype "passive"))
    )
    (net (code "83") (name "/STR_PD8_RF_TX") (class "Default")
      (node (ref "FdP") (pin "9") (pinfunction "9_9") (pintype "passive"))
      (node (ref "YAHOURT") (pin "9") (pinfunction "9_9") (pintype "passive"))
      (node (ref "rx") (pin "2") (pinfunction "2_2") (pintype "passive"))
    )
    (net (code "84") (name "/STR_PD9_RF_RX") (class "Default")
      (node (ref "FdP") (pin "12") (pinfunction "12_12") (pintype "passive"))
      (node (ref "YAHOURT") (pin "12") (pinfunction "12_12") (pintype "passive"))
      (node (ref "tx") (pin "2") (pinfunction "2_2") (pintype "passive"))
    )
    (net (code "85") (name "3V3") (class "Default")
      (node (ref "*") (pin "1") (pinfunction "VCC_1") (pintype "passive"))
      (node (ref "Cd0") (pin "2") (pinfunction "2_2") (pintype "passive"))
      (node (ref "Cd1") (pin "2") (pinfunction "2_2") (pintype "passive"))
      (node (ref "Cd2") (pin "2") (pinfunction "2_2") (pintype "passive"))
      (node (ref "Cd3") (pin "2") (pinfunction "2_2") (pintype "passive"))
      (node (ref "Cd3V_1") (pin "2") (pinfunction "2_2") (pintype "passive"))
      (node (ref "Cd4") (pin "2") (pinfunction "2_2") (pintype "passive"))
      (node (ref "Cd5") (pin "2") (pinfunction "2_2") (pintype "passive"))
      (node (ref "Cd6") (pin "2") (pinfunction "2_2") (pintype "passive"))
      (node (ref "Cd7") (pin "2") (pinfunction "2_2") (pintype "passive"))
      (node (ref "Cd8") (pin "2") (pinfunction "2_2") (pintype "passive"))
      (node (ref "Cd9") (pin "2") (pinfunction "2_2") (pintype "passive"))
      (node (ref "Cdlcd") (pin "1") (pinfunction "1_1") (pintype "passive"))
      (node (ref "P1") (pin "1") (pinfunction "Vdd_Target_1") (pintype "passive"))
      (node (ref "R_ledRetro3") (pin "1") (pinfunction "1_1") (pintype "passive"))
      (node (ref "Rnrst") (pin "2") (pinfunction "2_2") (pintype "passive"))
      (node (ref "RpuBP0") (pin "2") (pinfunction "2_2") (pintype "passive"))
      (node (ref "RpuBP1") (pin "2") (pinfunction "2_2") (pintype "passive"))
      (node (ref "RpuBP2") (pin "2") (pinfunction "2_2") (pintype "passive"))
      (node (ref "RpuBP3") (pin "2") (pinfunction "2_2") (pintype "passive"))
      (node (ref "RpuBP4") (pin "2") (pinfunction "2_2") (pintype "passive"))
      (node (ref "RpuBP5") (pin "2") (pinfunction "2_2") (pintype "passive"))
      (node (ref "RpuBPc") (pin "2") (pinfunction "2_2") (pintype "passive"))
      (node (ref "RpuBPpm") (pin "2") (pinfunction "2_2") (pintype "passive"))
      (node (ref "RpuBPrfu") (pin "2") (pinfunction "2_2") (pintype "passive"))
      (node (ref "RpuBPst") (pin "2") (pinfunction "2_2") (pintype "passive"))
      (node (ref "RpuSW0") (pin "2") (pinfunction "2_2") (pintype "passive"))
      (node (ref "RpuSW1") (pin "2") (pinfunction "2_2") (pintype "passive"))
      (node (ref "RpuSW10") (pin "2") (pinfunction "2_2") (pintype "passive"))
      (node (ref "RpuSW11") (pin "2") (pinfunction "2_2") (pintype "passive"))
      (node (ref "RpuSW12") (pin "2") (pinfunction "2_2") (pintype "passive"))
      (node (ref "RpuSW13") (pin "2") (pinfunction "2_2") (pintype "passive"))
      (node (ref "RpuSW14") (pin "2") (pinfunction "2_2") (pintype "passive"))
      (node (ref "RpuSW15") (pin "2") (pinfunction "2_2") (pintype "passive"))
      (node (ref "RpuSW16") (pin "2") (pinfunction "2_2") (pintype "passive"))
      (node (ref "RpuSW17") (pin "2") (pinfunction "2_2") (pintype "passive"))
      (node (ref "RpuSW18") (pin "2") (pinfunction "2_2") (pintype "passive"))
      (node (ref "RpuSW2") (pin "2") (pinfunction "2_2") (pintype "passive"))
      (node (ref "RpuSW3") (pin "2") (pinfunction "2_2") (pintype "passive"))
      (node (ref "RpuSW4") (pin "2") (pinfunction "2_2") (pintype "passive"))
      (node (ref "RpuSW5") (pin "2") (pinfunction "2_2") (pintype "passive"))
      (node (ref "RpuSW6") (pin "2") (pinfunction "2_2") (pintype "passive"))
      (node (ref "RpuSW7") (pin "2") (pinfunction "2_2") (pintype "passive"))
      (node (ref "RpuSW8") (pin "2") (pinfunction "2_2") (pintype "passive"))
      (node (ref "RpuSW9") (pin "2") (pinfunction "2_2") (pintype "passive"))
      (node (ref "RpuSWcolor") (pin "2") (pinfunction "2_2") (pintype "passive"))
      (node (ref "RpuSWlcd") (pin "2") (pinfunction "2_2") (pintype "passive"))
      (node (ref "STM32") (pin "100") (pinfunction "VDD_100") (pintype "power_in"))
      (node (ref "STM32") (pin "11") (pinfunction "VDD_11") (pintype "power_in"))
      (node (ref "STM32") (pin "19") (pinfunction "VDD_19") (pintype "power_in"))
      (node (ref "STM32") (pin "21") (pinfunction "VREF+_21") (pintype "power_in"))
      (node (ref "STM32") (pin "22") (pinfunction "VDDA_22") (pintype "power_in"))
      (node (ref "STM32") (pin "28") (pinfunction "VDD_28") (pintype "power_in"))
      (node (ref "STM32") (pin "50") (pinfunction "VDD_50") (pintype "power_in"))
      (node (ref "STM32") (pin "6") (pinfunction "VBAT_6") (pintype "power_in"))
      (node (ref "STM32") (pin "75") (pinfunction "VDD_75") (pintype "power_in"))
      (node (ref "STR_RpuU1rx") (pin "2") (pinfunction "2_2") (pintype "passive"))
      (node (ref "STR_RpuU1tx") (pin "2") (pinfunction "2_2") (pintype "passive"))
      (node (ref "STR_RupWAmI") (pin "2") (pinfunction "2_2") (pintype "passive"))
      (node (ref "Ureg_3V") (pin "3") (pinfunction "VOUT_3") (pintype "power_in"))
      (node (ref "YAHOURT") (pin "3") (pinfunction "3_3") (pintype "passive"))
    )
    (net (code "86") (name "5V") (class "Default")
      (node (ref "Cde_out") (pin "1") (pinfunction "1_1") (pintype "passive"))
      (node (ref "FdP_pwr") (pin "5") (pinfunction "5_5") (pintype "passive"))
      (node (ref "LED_color") (pin "1") (pinfunction "A_1") (pintype "passive"))
      (node (ref "LEDs") (pin "2") (pinfunction "2_2") (pintype "passive"))
      (node (ref "R_ledRetro5") (pin "1") (pinfunction "1_1") (pintype "passive"))
      (node (ref "Rcde") (pin "1") (pinfunction "1_1") (pintype "passive"))
      (node (ref "RledBir") (pin "2") (pinfunction "2_2") (pintype "passive"))
      (node (ref "RpuBir") (pin "2") (pinfunction "2_2") (pintype "passive"))
      (node (ref "RsLedBP0") (pin "2") (pinfunction "2_2") (pintype "passive"))
      (node (ref "RsLedBP1") (pin "2") (pinfunction "2_2") (pintype "passive"))
      (node (ref "RsLedBP2") (pin "2") (pinfunction "2_2") (pintype "passive"))
      (node (ref "RsLedBP3") (pin "2") (pinfunction "2_2") (pintype "passive"))
      (node (ref "RsLedBP4") (pin "2") (pinfunction "2_2") (pintype "passive"))
      (node (ref "RsLedBP5") (pin "2") (pinfunction "2_2") (pintype "passive"))
      (node (ref "RsLedBPc") (pin "2") (pinfunction "2_2") (pintype "passive"))
      (node (ref "RsLedBPpm") (pin "2") (pinfunction "2_2") (pintype "passive"))
      (node (ref "RsLedBPrfu") (pin "2") (pinfunction "2_2") (pintype "passive"))
      (node (ref "RsLedBPst") (pin "2") (pinfunction "2_2") (pintype "passive"))
      (node (ref "STR_CdCan1") (pin "2") (pinfunction "2_2") (pintype "passive"))
      (node (ref "STR_CdCan2") (pin "2") (pinfunction "2_2") (pintype "passive"))
      (node (ref "STR_Ucan") (pin "3") (pinfunction "VDD_3") (pintype "power_in"))
      (node (ref "Ureg_3V") (pin "1") (pinfunction "VIN_1") (pintype "power_in"))
      (node (ref "YAHOURT") (pin "2") (pinfunction "2_2") (pintype "passive"))
    )
    (net (code "87") (name "5VPerm") (class "Default")
      (node (ref "CdPerm") (pin "2") (pinfunction "2_2") (pintype "passive"))
      (node (ref "Cde_in") (pin "1") (pinfunction "1_1") (pintype "passive"))
      (node (ref "FdP_pwr") (pin "4") (pinfunction "4_4") (pintype "passive"))
      (node (ref "TR_5V") (pin "3") (pinfunction "+Vout1_3") (pintype "passive"))
    )
    (net (code "88") (name "5V_STR") (class "Default")
      (node (ref "FdP") (pin "2") (pinfunction "2_2") (pintype "passive"))
    )
    (net (code "89") (name "12V") (class "Default")
      (node (ref "12V_out") (pin "1") (pinfunction "1_1") (pintype "passive"))
      (node (ref "F1") (pin "1") (pinfunction "1_1") (pintype "passive"))
    )
    (net (code "90") (name "12Vhok") (class "Default")
      (node (ref "12V_Hokuyo") (pin "2") (pinfunction "2_2") (pintype "passive"))
      (node (ref "Dtransil") (pin "2") (pinfunction "K_2") (pintype "passive"))
      (node (ref "F1") (pin "2") (pinfunction "2_2") (pintype "passive"))
      (node (ref "Rhok") (pin "1") (pinfunction "1_1") (pintype "passive"))
      (node (ref "Rmes12+") (pin "2") (pinfunction "2_2") (pintype "passive"))
    )
    (net (code "91") (name "12Vin") (class "Default")
      (node (ref "12V_FdP") (pin "2") (pinfunction "2_2") (pintype "passive"))
      (node (ref "12V_in") (pin "1") (pinfunction "1_1") (pintype "passive"))
    )
    (net (code "92") (name "24VPsce") (class "Default")
      (node (ref "24V_T12") (pin "1") (pinfunction "1_1") (pintype "passive"))
      (node (ref "ARU_out") (pin "1") (pinfunction "1_1") (pintype "passive"))
      (node (ref "FdP_pwr") (pin "2") (pinfunction "2_2") (pintype "passive"))
      (node (ref "J11_24V") (pin "2") (pinfunction "2_2") (pintype "passive"))
      (node (ref "J14_24V") (pin "2") (pinfunction "2_2") (pintype "passive"))
      (node (ref "J5_24V") (pin "2") (pinfunction "2_2") (pintype "passive"))
      (node (ref "R24Psce") (pin "1") (pinfunction "1_1") (pintype "passive"))
      (node (ref "Rmes24p+") (pin "2") (pinfunction "2_2") (pintype "passive"))
    )
    (net (code "93") (name "24Vcordon") (class "Default")
      (node (ref "CORDON_24V") (pin "1") (pinfunction "1_1") (pintype "passive"))
      (node (ref "Dcordon") (pin "1") (pinfunction "A1_1") (pintype "passive"))
      (node (ref "Dcordon") (pin "3") (pinfunction "A2_3") (pintype "passive"))
    )
    (net (code "94") (name "24Vperm") (class "Default")
      (node (ref "ARU_in") (pin "1") (pinfunction "1_1") (pintype "passive"))
      (node (ref "BAT_24V") (pin "1") (pinfunction "1_1") (pintype "passive"))
      (node (ref "Batterie") (pin "2") (pinfunction "2_2") (pintype "passive"))
      (node (ref "CORDON_CHARGE") (pin "1") (pinfunction "1_1") (pintype "passive"))
      (node (ref "Chargeur") (pin "2") (pinfunction "2_2") (pintype "passive"))
      (node (ref "Dcordon") (pin "2") (pinfunction "K_2") (pintype "passive"))
      (node (ref "Dreverse") (pin "1") (pinfunction "A1_1") (pintype "passive"))
      (node (ref "Dreverse") (pin "3") (pinfunction "A2_3") (pintype "passive"))
      (node (ref "R24in") (pin "1") (pinfunction "1_1") (pintype "passive"))
      (node (ref "Rmes24+") (pin "2") (pinfunction "2_2") (pintype "passive"))
    )
    (net (code "95") (name "GND") (class "Default")
      (node (ref "*") (pin "2") (pinfunction "GND_2") (pintype "passive"))
      (node (ref "BP0") (pin "1") (pinfunction "1_1") (pintype "passive"))
      (node (ref "BP0") (pin "3") (pinfunction "3_3") (pintype "passive"))
      (node (ref "BP0") (pin "6") (pinfunction "-_6") (pintype "passive"))
      (node (ref "BP1") (pin "1") (pinfunction "1_1") (pintype "passive"))
      (node (ref "BP1") (pin "3") (pinfunction "3_3") (pintype "passive"))
      (node (ref "BP1") (pin "6") (pinfunction "-_6") (pintype "passive"))
      (node (ref "BP2") (pin "1") (pinfunction "1_1") (pintype "passive"))
      (node (ref "BP2") (pin "3") (pinfunction "3_3") (pintype "passive"))
      (node (ref "BP2") (pin "6") (pinfunction "-_6") (pintype "passive"))
      (node (ref "BP3") (pin "1") (pinfunction "1_1") (pintype "passive"))
      (node (ref "BP3") (pin "3") (pinfunction "3_3") (pintype "passive"))
      (node (ref "BP3") (pin "6") (pinfunction "-_6") (pintype "passive"))
      (node (ref "BP4") (pin "1") (pinfunction "1_1") (pintype "passive"))
      (node (ref "BP4") (pin "3") (pinfunction "3_3") (pintype "passive"))
      (node (ref "BP4") (pin "6") (pinfunction "-_6") (pintype "passive"))
      (node (ref "BP5") (pin "1") (pinfunction "1_1") (pintype "passive"))
      (node (ref "BP5") (pin "3") (pinfunction "3_3") (pintype "passive"))
      (node (ref "BP5") (pin "6") (pinfunction "-_6") (pintype "passive"))
      (node (ref "BPc") (pin "1") (pinfunction "1_1") (pintype "passive"))
      (node (ref "BPc") (pin "3") (pinfunction "3_3") (pintype "passive"))
      (node (ref "BPc") (pin "6") (pinfunction "-_6") (pintype "passive"))
      (node (ref "BPpm") (pin "1") (pinfunction "1_1") (pintype "passive"))
      (node (ref "BPpm") (pin "3") (pinfunction "3_3") (pintype "passive"))
      (node (ref "BPpm") (pin "6") (pinfunction "-_6") (pintype "passive"))
      (node (ref "BPrfu") (pin "1") (pinfunction "1_1") (pintype "passive"))
      (node (ref "BPrfu") (pin "3") (pinfunction "3_3") (pintype "passive"))
      (node (ref "BPrfu") (pin "6") (pinfunction "-_6") (pintype "passive"))
      (node (ref "BPst") (pin "1") (pinfunction "1_1") (pintype "passive"))
      (node (ref "BPst") (pin "3") (pinfunction "3_3") (pintype "passive"))
      (node (ref "BPst") (pin "6") (pinfunction "-_6") (pintype "passive"))
      (node (ref "C46") (pin "1") (pinfunction "1_1") (pintype "passive"))
      (node (ref "C47") (pin "1") (pinfunction "1_1") (pintype "passive"))
      (node (ref "C49") (pin "1") (pinfunction "1_1") (pintype "passive"))
      (node (ref "C50") (pin "1") (pinfunction "1_1") (pintype "passive"))
      (node (ref "Cd0") (pin "1") (pinfunction "1_1") (pintype "passive"))
      (node (ref "Cd1") (pin "1") (pinfunction "1_1") (pintype "passive"))
      (node (ref "Cd2") (pin "1") (pinfunction "1_1") (pintype "passive"))
      (node (ref "Cd3") (pin "1") (pinfunction "1_1") (pintype "passive"))
      (node (ref "Cd3V_1") (pin "1") (pinfunction "1_1") (pintype "passive"))
      (node (ref "Cd4") (pin "1") (pinfunction "1_1") (pintype "passive"))
      (node (ref "Cd5") (pin "1") (pinfunction "1_1") (pintype "passive"))
      (node (ref "Cd6") (pin "1") (pinfunction "1_1") (pintype "passive"))
      (node (ref "Cd7") (pin "1") (pinfunction "1_1") (pintype "passive"))
      (node (ref "Cd8") (pin "1") (pinfunction "1_1") (pintype "passive"))
      (node (ref "Cd9") (pin "1") (pinfunction "1_1") (pintype "passive"))
      (node (ref "CdPerm") (pin "1") (pinfunction "1_1") (pintype "passive"))
      (node (ref "Cdlcd") (pin "2") (pinfunction "2_2") (pintype "passive"))
      (node (ref "CfBP0") (pin "1") (pinfunction "1_1") (pintype "passive"))
      (node (ref "CfBP1") (pin "1") (pinfunction "1_1") (pintype "passive"))
      (node (ref "CfBP2") (pin "1") (pinfunction "1_1") (pintype "passive"))
      (node (ref "CfBP3") (pin "1") (pinfunction "1_1") (pintype "passive"))
      (node (ref "CfBP4") (pin "1") (pinfunction "1_1") (pintype "passive"))
      (node (ref "CfBP5") (pin "1") (pinfunction "1_1") (pintype "passive"))
      (node (ref "CfBPc") (pin "1") (pinfunction "1_1") (pintype "passive"))
      (node (ref "CfBPpm") (pin "1") (pinfunction "1_1") (pintype "passive"))
      (node (ref "CfBPrfu") (pin "1") (pinfunction "1_1") (pintype "passive"))
      (node (ref "CfBPst") (pin "1") (pinfunction "1_1") (pintype "passive"))
      (node (ref "CfBir") (pin "1") (pinfunction "1_1") (pintype "passive"))
      (node (ref "CfSW0") (pin "1") (pinfunction "1_1") (pintype "passive"))
      (node (ref "CfSW1") (pin "1") (pinfunction "1_1") (pintype "passive"))
      (node (ref "CfSW10") (pin "1") (pinfunction "1_1") (pintype "passive"))
      (node (ref "CfSW11") (pin "1") (pinfunction "1_1") (pintype "passive"))
      (node (ref "CfSW12") (pin "1") (pinfunction "1_1") (pintype "passive"))
      (node (ref "CfSW13") (pin "1") (pinfunction "1_1") (pintype "passive"))
      (node (ref "CfSW14") (pin "1") (pinfunction "1_1") (pintype "passive"))
      (node (ref "CfSW15") (pin "1") (pinfunction "1_1") (pintype "passive"))
      (node (ref "CfSW16") (pin "1") (pinfunction "1_1") (pintype "passive"))
      (node (ref "CfSW17") (pin "1") (pinfunction "1_1") (pintype "passive"))
      (node (ref "CfSW18") (pin "1") (pinfunction "1_1") (pintype "passive"))
      (node (ref "CfSW2") (pin "1") (pinfunction "1_1") (pintype "passive"))
      (node (ref "CfSW3") (pin "1") (pinfunction "1_1") (pintype "passive"))
      (node (ref "CfSW4") (pin "1") (pinfunction "1_1") (pintype "passive"))
      (node (ref "CfSW5") (pin "1") (pinfunction "1_1") (pintype "passive"))
      (node (ref "CfSW6") (pin "1") (pinfunction "1_1") (pintype "passive"))
      (node (ref "CfSW7") (pin "1") (pinfunction "1_1") (pintype "passive"))
      (node (ref "CfSW8") (pin "1") (pinfunction "1_1") (pintype "passive"))
      (node (ref "CfSW9") (pin "1") (pinfunction "1_1") (pintype "passive"))
      (node (ref "CfSWcolor") (pin "1") (pinfunction "1_1") (pintype "passive"))
      (node (ref "CfSWlcd") (pin "1") (pinfunction "1_1") (pintype "passive"))
      (node (ref "Cmes12") (pin "1") (pinfunction "1_1") (pintype "passive"))
      (node (ref "Cmes24") (pin "1") (pinfunction "1_1") (pintype "passive"))
      (node (ref "Cmes24p") (pin "1") (pinfunction "1_1") (pintype "passive"))
      (node (ref "Cnrst") (pin "1") (pinfunction "1_1") (pintype "passive"))
      (node (ref "Dcde") (pin "2") (pinfunction "K_2") (pintype "passive"))
      (node (ref "FdP") (pin "1") (pinfunction "1_1") (pintype "passive"))
      (node (ref "FdP") (pin "4") (pinfunction "4_4") (pintype "passive"))
      (node (ref "FdP_pwr") (pin "3") (pinfunction "3_3") (pintype "passive"))
      (node (ref "LEDs") (pin "1") (pinfunction "1_1") (pintype "passive"))
      (node (ref "Led0") (pin "2") (pinfunction "K_2") (pintype "passive"))
      (node (ref "Led1") (pin "2") (pinfunction "K_2") (pintype "passive"))
      (node (ref "Led2") (pin "2") (pinfunction "K_2") (pintype "passive"))
      (node (ref "Led3") (pin "2") (pinfunction "K_2") (pintype "passive"))
      (node (ref "Led4") (pin "2") (pinfunction "K_2") (pintype "passive"))
      (node (ref "Led5") (pin "2") (pinfunction "K_2") (pintype "passive"))
      (node (ref "P1") (pin "3") (pinfunction "GND_3") (pintype "passive"))
      (node (ref "Rmes12-") (pin "1") (pinfunction "1_1") (pintype "passive"))
      (node (ref "Rmes24-") (pin "1") (pinfunction "1_1") (pintype "passive"))
      (node (ref "Rmes24p-") (pin "1") (pinfunction "1_1") (pintype "passive"))
      (node (ref "STM32") (pin "10") (pinfunction "VSS_10") (pintype "power_in"))
      (node (ref "STM32") (pin "20") (pinfunction "VSSA_20") (pintype "power_in"))
      (node (ref "STM32") (pin "27") (pinfunction "VSS_27") (pintype "power_in"))
      (node (ref "STM32") (pin "74") (pinfunction "VSS_74") (pintype "power_in"))
      (node (ref "STM32") (pin "94") (pinfunction "BOOT0_94") (pintype "input"))
      (node (ref "STM32") (pin "99") (pinfunction "VSS_99") (pintype "power_in"))
      (node (ref "STR_CdCan1") (pin "1") (pinfunction "1_1") (pintype "passive"))
      (node (ref "STR_CdCan2") (pin "1") (pinfunction "1_1") (pintype "passive"))
      (node (ref "STR_Cu1rx") (pin "1") (pinfunction "1_1") (pintype "passive"))
      (node (ref "STR_RdwnWAmI") (pin "1") (pinfunction "1_1") (pintype "passive"))
      (node (ref "STR_UART1") (pin "5") (pinfunction "5_5") (pintype "passive"))
      (node (ref "STR_UART1") (pin "6") (pinfunction "6_6") (pintype "passive"))
      (node (ref "STR_Ucan") (pin "2") (pinfunction "VSS_2") (pintype "power_in"))
      (node (ref "STR_Ucan") (pin "8") (pinfunction "RS_8") (pintype "input"))
      (node (ref "STgnd") (pin "2") (pinfunction "2_2") (pintype "passive"))
      (node (ref "SW0") (pin "COMMON1") (pinfunction "COMMON1_COMMON1") (pintype "passive"))
      (node (ref "SW1") (pin "COMMON1") (pinfunction "COMMON1_COMMON1") (pintype "passive"))
      (node (ref "SW10") (pin "COMMON1") (pinfunction "COMMON1_COMMON1") (pintype "passive"))
      (node (ref "SW11") (pin "COMMON1") (pinfunction "COMMON1_COMMON1") (pintype "passive"))
      (node (ref "SW12") (pin "COMMON1") (pinfunction "COMMON1_COMMON1") (pintype "passive"))
      (node (ref "SW13") (pin "COMMON1") (pinfunction "COMMON1_COMMON1") (pintype "passive"))
      (node (ref "SW14") (pin "COMMON1") (pinfunction "COMMON1_COMMON1") (pintype "passive"))
      (node (ref "SW15") (pin "COMMON1") (pinfunction "COMMON1_COMMON1") (pintype "passive"))
      (node (ref "SW16") (pin "COMMON1") (pinfunction "COMMON1_COMMON1") (pintype "passive"))
      (node (ref "SW17") (pin "COMMON1") (pinfunction "COMMON1_COMMON1") (pintype "passive"))
      (node (ref "SW18") (pin "COMMON1") (pinfunction "COMMON1_COMMON1") (pintype "passive"))
      (node (ref "SW2") (pin "COMMON1") (pinfunction "COMMON1_COMMON1") (pintype "passive"))
      (node (ref "SW3") (pin "COMMON1") (pinfunction "COMMON1_COMMON1") (pintype "passive"))
      (node (ref "SW4") (pin "COMMON1") (pinfunction "COMMON1_COMMON1") (pintype "passive"))
      (node (ref "SW5") (pin "COMMON1") (pinfunction "COMMON1_COMMON1") (pintype "passive"))
      (node (ref "SW6") (pin "COMMON1") (pinfunction "COMMON1_COMMON1") (pintype "passive"))
      (node (ref "SW7") (pin "COMMON1") (pinfunction "COMMON1_COMMON1") (pintype "passive"))
      (node (ref "SW8") (pin "COMMON1") (pinfunction "COMMON1_COMMON1") (pintype "passive"))
      (node (ref "SW9") (pin "COMMON1") (pinfunction "COMMON1_COMMON1") (pintype "passive"))
      (node (ref "SWcolor") (pin "COMMON1") (pinfunction "COMMON1_COMMON1") (pintype "passive"))
      (node (ref "SWlcd") (pin "COMMON1") (pinfunction "COMMON1_COMMON1") (pintype "passive"))
      (node (ref "TR_5V") (pin "5") (pinfunction "-Vout1_5") (pintype "passive"))
      (node (ref "Ureg_3V") (pin "2") (pinfunction "GND_2") (pintype "power_in"))
      (node (ref "Ureg_3V") (pin "4") (pinfunction "GND_4") (pintype "power_in"))
      (node (ref "V1") (pin "1") (pinfunction "1_1") (pintype "passive"))
      (node (ref "V2") (pin "1") (pinfunction "1_1") (pintype "passive"))
      (node (ref "V3") (pin "1") (pinfunction "1_1") (pintype "passive"))
      (node (ref "V4") (pin "1") (pinfunction "1_1") (pintype "passive"))
      (node (ref "V5") (pin "1") (pinfunction "1_1") (pintype "passive"))
      (node (ref "V6") (pin "1") (pinfunction "1_1") (pintype "passive"))
      (node (ref "V7") (pin "1") (pinfunction "1_1") (pintype "passive"))
      (node (ref "V8") (pin "1") (pinfunction "1_1") (pintype "passive"))
      (node (ref "V9") (pin "1") (pinfunction "1_1") (pintype "passive"))
      (node (ref "YAHOURT") (pin "1") (pinfunction "1_1") (pintype "passive"))
      (node (ref "YAHOURT") (pin "4") (pinfunction "4_4") (pintype "passive"))
      (node (ref "biroute_gnd") (pin "1") (pinfunction "1_1") (pintype "passive"))
    )
    (net (code "96") (name "GND_12") (class "Default")
      (node (ref "12V_FdP") (pin "1") (pinfunction "1_1") (pintype "passive"))
      (node (ref "12V_Hokuyo") (pin "1") (pinfunction "1_1") (pintype "passive"))
      (node (ref "Dhok") (pin "2") (pinfunction "K_2") (pintype "passive"))
      (node (ref "Dtransil") (pin "1") (pinfunction "A_1") (pintype "passive"))
    )
    (net (code "97") (name "GND_24") (class "Default")
      (node (ref "BAT_GND") (pin "1") (pinfunction "1_1") (pintype "passive"))
      (node (ref "Batterie") (pin "1") (pinfunction "1_1") (pintype "passive"))
      (node (ref "CORDON_GND") (pin "1") (pinfunction "1_1") (pintype "passive"))
      (node (ref "Cd24VCDE") (pin "1") (pinfunction "1_1") (pintype "passive"))
      (node (ref "Chargeur") (pin "1") (pinfunction "1_1") (pintype "passive"))
      (node (ref "D24Psce") (pin "2") (pinfunction "K_2") (pintype "passive"))
      (node (ref "D24in") (pin "2") (pinfunction "K_2") (pintype "passive"))
      (node (ref "FdP_pwr") (pin "1") (pinfunction "1_1") (pintype "passive"))
      (node (ref "GND_T12") (pin "1") (pinfunction "1_1") (pintype "passive"))
      (node (ref "J11_24V") (pin "1") (pinfunction "1_1") (pintype "passive"))
      (node (ref "J14_24V") (pin "1") (pinfunction "1_1") (pintype "passive"))
      (node (ref "J5_24V") (pin "1") (pinfunction "1_1") (pintype "passive"))
      (node (ref "STgnd") (pin "1") (pinfunction "1_1") (pintype "passive"))
      (node (ref "TR_5V") (pin "2") (pinfunction "-Vin_2") (pintype "passive"))
    )
    (net (code "98") (name "Net-(*-LED)") (class "Default")
      (node (ref "*") (pin "8") (pinfunction "LED_8") (pintype "passive"))
      (node (ref "R_ledRetro3") (pin "2") (pinfunction "2_2") (pintype "passive"))
      (node (ref "R_ledRetro5") (pin "2") (pinfunction "2_2") (pintype "passive"))
    )
    (net (code "99") (name "Net-(BP0-+)") (class "Default")
      (node (ref "BP0") (pin "5") (pinfunction "+_5") (pintype "passive"))
      (node (ref "RsLedBP0") (pin "1") (pinfunction "1_1") (pintype "passive"))
    )
    (net (code "100") (name "Net-(BP0-3-Pad2)") (class "Default")
      (node (ref "BP0") (pin "2") (pinfunction "3_2") (pintype "passive"))
      (node (ref "BP0") (pin "4") (pinfunction "4_4") (pintype "passive"))
      (node (ref "RpuBP0") (pin "1") (pinfunction "1_1") (pintype "passive"))
      (node (ref "RsBP0") (pin "1") (pinfunction "1_1") (pintype "passive"))
    )
    (net (code "101") (name "Net-(BP1-+)") (class "Default")
      (node (ref "BP1") (pin "5") (pinfunction "+_5") (pintype "passive"))
      (node (ref "RsLedBP1") (pin "1") (pinfunction "1_1") (pintype "passive"))
    )
    (net (code "102") (name "Net-(BP1-3-Pad2)") (class "Default")
      (node (ref "BP1") (pin "2") (pinfunction "3_2") (pintype "passive"))
      (node (ref "BP1") (pin "4") (pinfunction "4_4") (pintype "passive"))
      (node (ref "RpuBP1") (pin "1") (pinfunction "1_1") (pintype "passive"))
      (node (ref "RsBP1") (pin "1") (pinfunction "1_1") (pintype "passive"))
    )
    (net (code "103") (name "Net-(BP2-+)") (class "Default")
      (node (ref "BP2") (pin "5") (pinfunction "+_5") (pintype "passive"))
      (node (ref "RsLedBP2") (pin "1") (pinfunction "1_1") (pintype "passive"))
    )
    (net (code "104") (name "Net-(BP2-3-Pad2)") (class "Default")
      (node (ref "BP2") (pin "2") (pinfunction "3_2") (pintype "passive"))
      (node (ref "BP2") (pin "4") (pinfunction "4_4") (pintype "passive"))
      (node (ref "RpuBP2") (pin "1") (pinfunction "1_1") (pintype "passive"))
      (node (ref "RsBP2") (pin "1") (pinfunction "1_1") (pintype "passive"))
    )
    (net (code "105") (name "Net-(BP3-+)") (class "Default")
      (node (ref "BP3") (pin "5") (pinfunction "+_5") (pintype "passive"))
      (node (ref "RsLedBP3") (pin "1") (pinfunction "1_1") (pintype "passive"))
    )
    (net (code "106") (name "Net-(BP3-3-Pad2)") (class "Default")
      (node (ref "BP3") (pin "2") (pinfunction "3_2") (pintype "passive"))
      (node (ref "BP3") (pin "4") (pinfunction "4_4") (pintype "passive"))
      (node (ref "RpuBP3") (pin "1") (pinfunction "1_1") (pintype "passive"))
      (node (ref "RsBP3") (pin "1") (pinfunction "1_1") (pintype "passive"))
    )
    (net (code "107") (name "Net-(BP4-+)") (class "Default")
      (node (ref "BP4") (pin "5") (pinfunction "+_5") (pintype "passive"))
      (node (ref "RsLedBP4") (pin "1") (pinfunction "1_1") (pintype "passive"))
    )
    (net (code "108") (name "Net-(BP4-3-Pad2)") (class "Default")
      (node (ref "BP4") (pin "2") (pinfunction "3_2") (pintype "passive"))
      (node (ref "BP4") (pin "4") (pinfunction "4_4") (pintype "passive"))
      (node (ref "RpuBP4") (pin "1") (pinfunction "1_1") (pintype "passive"))
      (node (ref "RsBP4") (pin "1") (pinfunction "1_1") (pintype "passive"))
    )
    (net (code "109") (name "Net-(BP5-+)") (class "Default")
      (node (ref "BP5") (pin "5") (pinfunction "+_5") (pintype "passive"))
      (node (ref "RsLedBP5") (pin "1") (pinfunction "1_1") (pintype "passive"))
    )
    (net (code "110") (name "Net-(BP5-3-Pad2)") (class "Default")
      (node (ref "BP5") (pin "2") (pinfunction "3_2") (pintype "passive"))
      (node (ref "BP5") (pin "4") (pinfunction "4_4") (pintype "passive"))
      (node (ref "RpuBP5") (pin "1") (pinfunction "1_1") (pintype "passive"))
      (node (ref "RsBP5") (pin "1") (pinfunction "1_1") (pintype "passive"))
    )
    (net (code "111") (name "Net-(BPc-+)") (class "Default")
      (node (ref "BPc") (pin "5") (pinfunction "+_5") (pintype "passive"))
      (node (ref "RsLedBPc") (pin "1") (pinfunction "1_1") (pintype "passive"))
    )
    (net (code "112") (name "Net-(BPc-3-Pad2)") (class "Default")
      (node (ref "BPc") (pin "2") (pinfunction "3_2") (pintype "passive"))
      (node (ref "BPc") (pin "4") (pinfunction "4_4") (pintype "passive"))
      (node (ref "RpuBPc") (pin "1") (pinfunction "1_1") (pintype "passive"))
      (node (ref "RsBPc") (pin "1") (pinfunction "1_1") (pintype "passive"))
    )
    (net (code "113") (name "Net-(BPpm-+)") (class "Default")
      (node (ref "BPpm") (pin "5") (pinfunction "+_5") (pintype "passive"))
      (node (ref "RsLedBPpm") (pin "1") (pinfunction "1_1") (pintype "passive"))
    )
    (net (code "114") (name "Net-(BPpm-3-Pad2)") (class "Default")
      (node (ref "BPpm") (pin "2") (pinfunction "3_2") (pintype "passive"))
      (node (ref "BPpm") (pin "4") (pinfunction "4_4") (pintype "passive"))
      (node (ref "RpuBPpm") (pin "1") (pinfunction "1_1") (pintype "passive"))
      (node (ref "RsBPpm") (pin "1") (pinfunction "1_1") (pintype "passive"))
    )
    (net (code "115") (name "Net-(BPrfu-+)") (class "Default")
      (node (ref "BPrfu") (pin "5") (pinfunction "+_5") (pintype "passive"))
      (node (ref "RsLedBPrfu") (pin "1") (pinfunction "1_1") (pintype "passive"))
    )
    (net (code "116") (name "Net-(BPrfu-3-Pad2)") (class "Default")
      (node (ref "BPrfu") (pin "2") (pinfunction "3_2") (pintype "passive"))
      (node (ref "BPrfu") (pin "4") (pinfunction "4_4") (pintype "passive"))
      (node (ref "RpuBPrfu") (pin "1") (pinfunction "1_1") (pintype "passive"))
      (node (ref "RsBPrfu") (pin "1") (pinfunction "1_1") (pintype "passive"))
    )
    (net (code "117") (name "Net-(BPst-+)") (class "Default")
      (node (ref "BPst") (pin "5") (pinfunction "+_5") (pintype "passive"))
      (node (ref "RsLedBPst") (pin "1") (pinfunction "1_1") (pintype "passive"))
    )
    (net (code "118") (name "Net-(BPst-3-Pad2)") (class "Default")
      (node (ref "BPst") (pin "2") (pinfunction "3_2") (pintype "passive"))
      (node (ref "BPst") (pin "4") (pinfunction "4_4") (pintype "passive"))
      (node (ref "RpuBPst") (pin "1") (pinfunction "1_1") (pintype "passive"))
      (node (ref "RsBPst") (pin "1") (pinfunction "1_1") (pintype "passive"))
    )
    (net (code "119") (name "Net-(D24Psce-A)") (class "Default")
      (node (ref "D24Psce") (pin "1") (pinfunction "A_1") (pintype "passive"))
      (node (ref "R24Psce") (pin "2") (pinfunction "2_2") (pintype "passive"))
    )
    (net (code "120") (name "Net-(D24in-A)") (class "Default")
      (node (ref "D24in") (pin "1") (pinfunction "A_1") (pintype "passive"))
      (node (ref "R24in") (pin "2") (pinfunction "2_2") (pintype "passive"))
    )
    (net (code "121") (name "Net-(Dcde-A)") (class "Default")
      (node (ref "Dcde") (pin "1") (pinfunction "A_1") (pintype "passive"))
      (node (ref "Rcde") (pin "2") (pinfunction "2_2") (pintype "passive"))
    )
    (net (code "122") (name "Net-(Dhok-A)") (class "Default")
      (node (ref "Dhok") (pin "1") (pinfunction "A_1") (pintype "passive"))
      (node (ref "Rhok") (pin "2") (pinfunction "2_2") (pintype "passive"))
    )
    (net (code "123") (name "Net-(Dreverse-K)") (class "Default")
      (node (ref "Cd24VCDE") (pin "2") (pinfunction "2_2") (pintype "passive"))
      (node (ref "Dreverse") (pin "2") (pinfunction "K_2") (pintype "passive"))
      (node (ref "TR_5V") (pin "1") (pinfunction "+Vin_1") (pintype "passive"))
    )
    (net (code "124") (name "Net-(LED_color-C1)") (class "Default")
      (node (ref "LED_color") (pin "4") (pinfunction "C1_4") (pintype "passive"))
      (node (ref "RGreen") (pin "2") (pinfunction "2_2") (pintype "passive"))
    )
    (net (code "125") (name "Net-(LED_color-C2)") (class "Default")
      (node (ref "LED_color") (pin "3") (pinfunction "C2_3") (pintype "passive"))
      (node (ref "Rred") (pin "2") (pinfunction "2_2") (pintype "passive"))
    )
    (net (code "126") (name "Net-(LED_color-C3)") (class "Default")
      (node (ref "LED_color") (pin "2") (pinfunction "C3_2") (pintype "passive"))
      (node (ref "RBlue") (pin "2") (pinfunction "2_2") (pintype "passive"))
    )
    (net (code "127") (name "Net-(Led0-A)") (class "Default")
      (node (ref "Led0") (pin "1") (pinfunction "A_1") (pintype "passive"))
      (node (ref "Rled0") (pin "1") (pinfunction "1_1") (pintype "passive"))
    )
    (net (code "128") (name "Net-(Led1-A)") (class "Default")
      (node (ref "Led1") (pin "1") (pinfunction "A_1") (pintype "passive"))
      (node (ref "Rled1") (pin "1") (pinfunction "1_1") (pintype "passive"))
    )
    (net (code "129") (name "Net-(Led2-A)") (class "Default")
      (node (ref "Led2") (pin "1") (pinfunction "A_1") (pintype "passive"))
      (node (ref "Rled2") (pin "1") (pinfunction "1_1") (pintype "passive"))
    )
    (net (code "130") (name "Net-(Led3-A)") (class "Default")
      (node (ref "Led3") (pin "1") (pinfunction "A_1") (pintype "passive"))
      (node (ref "Rled3") (pin "1") (pinfunction "1_1") (pintype "passive"))
    )
    (net (code "131") (name "Net-(Led4-A)") (class "Default")
      (node (ref "Led4") (pin "1") (pinfunction "A_1") (pintype "passive"))
      (node (ref "Rled4") (pin "1") (pinfunction "1_1") (pintype "passive"))
    )
    (net (code "132") (name "Net-(Led5-A)") (class "Default")
      (node (ref "Led5") (pin "1") (pinfunction "A_1") (pintype "passive"))
      (node (ref "Rled5") (pin "1") (pinfunction "1_1") (pintype "passive"))
    )
    (net (code "133") (name "Net-(RledBir-Pad1)") (class "Default")
      (node (ref "RledBir") (pin "1") (pinfunction "1_1") (pintype "passive"))
      (node (ref "birouteLed") (pin "1") (pinfunction "1_1") (pintype "passive"))
    )
    (net (code "134") (name "Net-(Rmes12+-Pad1)") (class "Default")
      (node (ref "Rmes12+") (pin "1") (pinfunction "1_1") (pintype "passive"))
      (node (ref "Rmes12-") (pin "2") (pinfunction "2_2") (pintype "passive"))
      (node (ref "Rsme12") (pin "1") (pinfunction "1_1") (pintype "passive"))
    )
    (net (code "135") (name "Net-(Rmes24+-Pad1)") (class "Default")
      (node (ref "Rmes24+") (pin "1") (pinfunction "1_1") (pintype "passive"))
      (node (ref "Rmes24-") (pin "2") (pinfunction "2_2") (pintype "passive"))
      (node (ref "Rsme24") (pin "1") (pinfunction "1_1") (pintype "passive"))
    )
    (net (code "136") (name "Net-(Rmes24p+-Pad1)") (class "Default")
      (node (ref "Rmes24p+") (pin "1") (pinfunction "1_1") (pintype "passive"))
      (node (ref "Rmes24p-") (pin "2") (pinfunction "2_2") (pintype "passive"))
      (node (ref "Rsme24p") (pin "1") (pinfunction "1_1") (pintype "passive"))
    )
    (net (code "137") (name "Net-(RpuBir-Pad1)") (class "Default")
      (node (ref "RpuBir") (pin "1") (pinfunction "1_1") (pintype "passive"))
      (node (ref "RsBir") (pin "1") (pinfunction "1_1") (pintype "passive"))
      (node (ref "biroute") (pin "1") (pinfunction "1_1") (pintype "passive"))
    )
    (net (code "138") (name "Net-(RpuSW0-Pad1)") (class "Default")
      (node (ref "RpuSW0") (pin "1") (pinfunction "1_1") (pintype "passive"))
      (node (ref "RsSW0") (pin "1") (pinfunction "1_1") (pintype "passive"))
      (node (ref "SW0") (pin "NC1") (pinfunction "NC1_NC1") (pintype "passive"))
    )
    (net (code "139") (name "Net-(RpuSW1-Pad1)") (class "Default")
      (node (ref "RpuSW1") (pin "1") (pinfunction "1_1") (pintype "passive"))
      (node (ref "RsSW1") (pin "1") (pinfunction "1_1") (pintype "passive"))
      (node (ref "SW1") (pin "NC1") (pinfunction "NC1_NC1") (pintype "passive"))
    )
    (net (code "140") (name "Net-(RpuSW2-Pad1)") (class "Default")
      (node (ref "RpuSW2") (pin "1") (pinfunction "1_1") (pintype "passive"))
      (node (ref "RsSW2") (pin "1") (pinfunction "1_1") (pintype "passive"))
      (node (ref "SW2") (pin "NC1") (pinfunction "NC1_NC1") (pintype "passive"))
    )
    (net (code "141") (name "Net-(RpuSW3-Pad1)") (class "Default")
      (node (ref "RpuSW3") (pin "1") (pinfunction "1_1") (pintype "passive"))
      (node (ref "RsSW3") (pin "1") (pinfunction "1_1") (pintype "passive"))
      (node (ref "SW3") (pin "NC1") (pinfunction "NC1_NC1") (pintype "passive"))
    )
    (net (code "142") (name "Net-(RpuSW4-Pad1)") (class "Default")
      (node (ref "RpuSW4") (pin "1") (pinfunction "1_1") (pintype "passive"))
      (node (ref "RsSW4") (pin "1") (pinfunction "1_1") (pintype "passive"))
      (node (ref "SW4") (pin "NC1") (pinfunction "NC1_NC1") (pintype "passive"))
    )
    (net (code "143") (name "Net-(RpuSW5-Pad1)") (class "Default")
      (node (ref "RpuSW5") (pin "1") (pinfunction "1_1") (pintype "passive"))
      (node (ref "RsSW5") (pin "1") (pinfunction "1_1") (pintype "passive"))
      (node (ref "SW5") (pin "NC1") (pinfunction "NC1_NC1") (pintype "passive"))
    )
    (net (code "144") (name "Net-(RpuSW6-Pad1)") (class "Default")
      (node (ref "RpuSW6") (pin "1") (pinfunction "1_1") (pintype "passive"))
      (node (ref "RsSW6") (pin "1") (pinfunction "1_1") (pintype "passive"))
      (node (ref "SW6") (pin "NC1") (pinfunction "NC1_NC1") (pintype "passive"))
    )
    (net (code "145") (name "Net-(RpuSW7-Pad1)") (class "Default")
      (node (ref "RpuSW7") (pin "1") (pinfunction "1_1") (pintype "passive"))
      (node (ref "RsSW7") (pin "1") (pinfunction "1_1") (pintype "passive"))
      (node (ref "SW7") (pin "NC1") (pinfunction "NC1_NC1") (pintype "passive"))
    )
    (net (code "146") (name "Net-(RpuSW8-Pad1)") (class "Default")
      (node (ref "RpuSW8") (pin "1") (pinfunction "1_1") (pintype "passive"))
      (node (ref "RsSW8") (pin "1") (pinfunction "1_1") (pintype "passive"))
      (node (ref "SW8") (pin "NC1") (pinfunction "NC1_NC1") (pintype "passive"))
    )
    (net (code "147") (name "Net-(RpuSW9-Pad1)") (class "Default")
      (node (ref "RpuSW9") (pin "1") (pinfunction "1_1") (pintype "passive"))
      (node (ref "RsSW9") (pin "1") (pinfunction "1_1") (pintype "passive"))
      (node (ref "SW9") (pin "NC1") (pinfunction "NC1_NC1") (pintype "passive"))
    )
    (net (code "148") (name "Net-(RpuSW10-Pad1)") (class "Default")
      (node (ref "RpuSW10") (pin "1") (pinfunction "1_1") (pintype "passive"))
      (node (ref "RsSW10") (pin "1") (pinfunction "1_1") (pintype "passive"))
      (node (ref "SW10") (pin "NC1") (pinfunction "NC1_NC1") (pintype "passive"))
    )
    (net (code "149") (name "Net-(RpuSW11-Pad1)") (class "Default")
      (node (ref "RpuSW11") (pin "1") (pinfunction "1_1") (pintype "passive"))
      (node (ref "RsSW11") (pin "1") (pinfunction "1_1") (pintype "passive"))
      (node (ref "SW11") (pin "NC1") (pinfunction "NC1_NC1") (pintype "passive"))
    )
    (net (code "150") (name "Net-(RpuSW12-Pad1)") (class "Default")
      (node (ref "RpuSW12") (pin "1") (pinfunction "1_1") (pintype "passive"))
      (node (ref "RsSW12") (pin "1") (pinfunction "1_1") (pintype "passive"))
      (node (ref "SW12") (pin "NC1") (pinfunction "NC1_NC1") (pintype "passive"))
    )
    (net (code "151") (name "Net-(RpuSW13-Pad1)") (class "Default")
      (node (ref "RpuSW13") (pin "1") (pinfunction "1_1") (pintype "passive"))
      (node (ref "RsSW13") (pin "1") (pinfunction "1_1") (pintype "passive"))
      (node (ref "SW13") (pin "NC1") (pinfunction "NC1_NC1") (pintype "passive"))
    )
    (net (code "152") (name "Net-(RpuSW14-Pad1)") (class "Default")
      (node (ref "RpuSW14") (pin "1") (pinfunction "1_1") (pintype "passive"))
      (node (ref "RsSW14") (pin "1") (pinfunction "1_1") (pintype "passive"))
      (node (ref "SW14") (pin "NC1") (pinfunction "NC1_NC1") (pintype "passive"))
    )
    (net (code "153") (name "Net-(RpuSW15-Pad1)") (class "Default")
      (node (ref "RpuSW15") (pin "1") (pinfunction "1_1") (pintype "passive"))
      (node (ref "RsSW15") (pin "1") (pinfunction "1_1") (pintype "passive"))
      (node (ref "SW15") (pin "NC1") (pinfunction "NC1_NC1") (pintype "passive"))
    )
    (net (code "154") (name "Net-(RpuSW16-Pad1)") (class "Default")
      (node (ref "RpuSW16") (pin "1") (pinfunction "1_1") (pintype "passive"))
      (node (ref "RsSW16") (pin "1") (pinfunction "1_1") (pintype "passive"))
      (node (ref "SW16") (pin "NC1") (pinfunction "NC1_NC1") (pintype "passive"))
    )
    (net (code "155") (name "Net-(RpuSW17-Pad1)") (class "Default")
      (node (ref "RpuSW17") (pin "1") (pinfunction "1_1") (pintype "passive"))
      (node (ref "RsSW17") (pin "1") (pinfunction "1_1") (pintype "passive"))
      (node (ref "SW17") (pin "NC1") (pinfunction "NC1_NC1") (pintype "passive"))
    )
    (net (code "156") (name "Net-(RpuSW18-Pad1)") (class "Default")
      (node (ref "RpuSW18") (pin "1") (pinfunction "1_1") (pintype "passive"))
      (node (ref "RsSW18") (pin "1") (pinfunction "1_1") (pintype "passive"))
      (node (ref "SW18") (pin "NC1") (pinfunction "NC1_NC1") (pintype "passive"))
    )
    (net (code "157") (name "Net-(RpuSWcolor-Pad1)") (class "Default")
      (node (ref "RpuSWcolor") (pin "1") (pinfunction "1_1") (pintype "passive"))
      (node (ref "RsSWcolor") (pin "1") (pinfunction "1_1") (pintype "passive"))
      (node (ref "SWcolor") (pin "NC1") (pinfunction "NC1_NC1") (pintype "passive"))
    )
    (net (code "158") (name "Net-(RpuSWlcd-Pad1)") (class "Default")
      (node (ref "RpuSWlcd") (pin "1") (pinfunction "1_1") (pintype "passive"))
      (node (ref "RsSWlcd") (pin "1") (pinfunction "1_1") (pintype "passive"))
      (node (ref "SWlcd") (pin "NC1") (pinfunction "NC1_NC1") (pintype "passive"))
    )
    (net (code "159") (name "Net-(STM32A-PD8)") (class "Default")
      (node (ref "STM32") (pin "55") (pinfunction "PD8_55") (pintype "bidirectional"))
      (node (ref "tx") (pin "1") (pinfunction "1_1") (pintype "passive"))
    )
    (net (code "160") (name "Net-(STM32A-PD9)") (class "Default")
      (node (ref "STM32") (pin "56") (pinfunction "PD9_56") (pintype "bidirectional"))
      (node (ref "rx") (pin "1") (pinfunction "1_1") (pintype "passive"))
    )
    (net (code "161") (name "Net-(STM32A-PH0-OSC_IN(PH0))") (class "Default")
      (node (ref "C46") (pin "2") (pinfunction "2_2") (pintype "passive"))
      (node (ref "STM32") (pin "12") (pinfunction "PH0-OSC_IN(PH0)_12") (pintype "bidirectional"))
      (node (ref "Y1") (pin "2") (pinfunction "OSC2_2") (pintype "passive"))
    )
    (net (code "162") (name "Net-(STM32A-PH1-OSC_OUT(PH1))") (class "Default")
      (node (ref "C47") (pin "2") (pinfunction "2_2") (pintype "passive"))
      (node (ref "STM32") (pin "13") (pinfunction "PH1-OSC_OUT(PH1)_13") (pintype "bidirectional"))
      (node (ref "Y1") (pin "1") (pinfunction "OSC1_1") (pintype "passive"))
    )
    (net (code "163") (name "Net-(STM32A-VCAP_1)") (class "Default")
      (node (ref "C49") (pin "2") (pinfunction "2_2") (pintype "passive"))
      (node (ref "STM32") (pin "49") (pinfunction "VCAP_1_49") (pintype "power_in"))
    )
    (net (code "164") (name "Net-(STM32A-VCAP_2)") (class "Default")
      (node (ref "C50") (pin "2") (pinfunction "2_2") (pintype "passive"))
      (node (ref "STM32") (pin "73") (pinfunction "VCAP_2_73") (pintype "power_in"))
    )
    (net (code "165") (name "Net-(STR_RpuU1tx-Pad1)") (class "Default")
      (node (ref "STR_RpuU1tx") (pin "1") (pinfunction "1_1") (pintype "passive"))
      (node (ref "STR_RsU1tx") (pin "1") (pinfunction "1_1") (pintype "passive"))
      (node (ref "STR_UART1") (pin "3") (pinfunction "3_3") (pintype "passive"))
    )
    (net (code "166") (name "Net-(STR_Rsu1rx-Pad2)") (class "Default")
      (node (ref "STR_Rsu1rx") (pin "2") (pinfunction "2_2") (pintype "passive"))
      (node (ref "STR_UART1") (pin "4") (pinfunction "4_4") (pintype "passive"))
    )
    (net (code "167") (name "unconnected-(*-SD_CS-Pad18)") (class "Default")
      (node (ref "*") (pin "18") (pinfunction "SD_CS_18") (pintype "passive"))
    )
    (net (code "168") (name "unconnected-(*-SD_MISO-Pad16)") (class "Default")
      (node (ref "*") (pin "16") (pinfunction "SD_MISO_16") (pintype "passive"))
    )
    (net (code "169") (name "unconnected-(*-SD_MOSI-Pad17)") (class "Default")
      (node (ref "*") (pin "17") (pinfunction "SD_MOSI_17") (pintype "passive"))
    )
    (net (code "170") (name "unconnected-(*-SD_SCK-Pad15)") (class "Default")
      (node (ref "*") (pin "15") (pinfunction "SD_SCK_15") (pintype "passive"))
    )
    (net (code "171") (name "unconnected-(STM32A-PA2-Pad25)") (class "Default")
      (node (ref "STM32") (pin "25") (pinfunction "PA2_25") (pintype "bidirectional"))
    )
    (net (code "172") (name "unconnected-(STM32A-PA8-Pad67)") (class "Default")
      (node (ref "STM32") (pin "67") (pinfunction "PA8_67") (pintype "bidirectional"))
    )
    (net (code "173") (name "unconnected-(STM32A-PA15(JTDI)-Pad77)") (class "Default")
      (node (ref "STM32") (pin "77") (pinfunction "PA15(JTDI)_77") (pintype "bidirectional"))
    )
    (net (code "174") (name "unconnected-(STM32A-PC12-Pad80)") (class "Default")
      (node (ref "STM32") (pin "80") (pinfunction "PC12_80") (pintype "bidirectional"))
    )
    (net (code "175") (name "unconnected-(STM32A-PC14-OSC32_IN(PC14)-Pad8)") (class "Default")
      (node (ref "STM32") (pin "8") (pinfunction "PC14-OSC32_IN(PC14)_8") (pintype "bidirectional"))
    )
    (net (code "176") (name "unconnected-(STM32A-PC15-OSC32_OUT(PC15)-Pad9)") (class "Default")
      (node (ref "STM32") (pin "9") (pinfunction "PC15-OSC32_OUT(PC15)_9") (pintype "bidirectional"))
    )
    (net (code "177") (name "unconnected-(STM32A-PE2-Pad1)") (class "Default")
      (node (ref "STM32") (pin "1") (pinfunction "PE2_1") (pintype "bidirectional"))
    )
    (net (code "178") (name "unconnected-(STR_UART1-Pad1)") (class "Default")
      (node (ref "STR_UART1") (pin "1") (pinfunction "1_1") (pintype "passive+no_connect"))
    )
    (net (code "179") (name "unconnected-(STR_UART1-Pad2)") (class "Default")
      (node (ref "STR_UART1") (pin "2") (pinfunction "2_2") (pintype "passive+no_connect"))
    )
    (net (code "180") (name "unconnected-(STR_Ucan-VREF-Pad5)") (class "Default")
      (node (ref "STR_Ucan") (pin "5") (pinfunction "VREF_5") (pintype "output"))
    )
    (net (code "181") (name "unconnected-(SW0-PadNO1)") (class "Default")
      (node (ref "SW0") (pin "NO1") (pinfunction "NO1_NO1") (pintype "passive+no_connect"))
    )
    (net (code "182") (name "unconnected-(SW1-PadNO1)") (class "Default")
      (node (ref "SW1") (pin "NO1") (pinfunction "NO1_NO1") (pintype "passive+no_connect"))
    )
    (net (code "183") (name "unconnected-(SW2-PadNO1)") (class "Default")
      (node (ref "SW2") (pin "NO1") (pinfunction "NO1_NO1") (pintype "passive+no_connect"))
    )
    (net (code "184") (name "unconnected-(SW3-PadNO1)") (class "Default")
      (node (ref "SW3") (pin "NO1") (pinfunction "NO1_NO1") (pintype "passive+no_connect"))
    )
    (net (code "185") (name "unconnected-(SW4-PadNO1)") (class "Default")
      (node (ref "SW4") (pin "NO1") (pinfunction "NO1_NO1") (pintype "passive+no_connect"))
    )
    (net (code "186") (name "unconnected-(SW5-PadNO1)") (class "Default")
      (node (ref "SW5") (pin "NO1") (pinfunction "NO1_NO1") (pintype "passive+no_connect"))
    )
    (net (code "187") (name "unconnected-(SW6-PadNO1)") (class "Default")
      (node (ref "SW6") (pin "NO1") (pinfunction "NO1_NO1") (pintype "passive+no_connect"))
    )
    (net (code "188") (name "unconnected-(SW7-PadNO1)") (class "Default")
      (node (ref "SW7") (pin "NO1") (pinfunction "NO1_NO1") (pintype "passive+no_connect"))
    )
    (net (code "189") (name "unconnected-(SW8-PadNO1)") (class "Default")
      (node (ref "SW8") (pin "NO1") (pinfunction "NO1_NO1") (pintype "passive+no_connect"))
    )
    (net (code "190") (name "unconnected-(SW9-PadNO1)") (class "Default")
      (node (ref "SW9") (pin "NO1") (pinfunction "NO1_NO1") (pintype "passive+no_connect"))
    )
    (net (code "191") (name "unconnected-(SW10-PadNO1)") (class "Default")
      (node (ref "SW10") (pin "NO1") (pinfunction "NO1_NO1") (pintype "passive+no_connect"))
    )
    (net (code "192") (name "unconnected-(SW11-PadNO1)") (class "Default")
      (node (ref "SW11") (pin "NO1") (pinfunction "NO1_NO1") (pintype "passive+no_connect"))
    )
    (net (code "193") (name "unconnected-(SW12-PadNO1)") (class "Default")
      (node (ref "SW12") (pin "NO1") (pinfunction "NO1_NO1") (pintype "passive+no_connect"))
    )
    (net (code "194") (name "unconnected-(SW13-PadNO1)") (class "Default")
      (node (ref "SW13") (pin "NO1") (pinfunction "NO1_NO1") (pintype "passive+no_connect"))
    )
    (net (code "195") (name "unconnected-(SW14-PadNO1)") (class "Default")
      (node (ref "SW14") (pin "NO1") (pinfunction "NO1_NO1") (pintype "passive+no_connect"))
    )
    (net (code "196") (name "unconnected-(SW15-PadNO1)") (class "Default")
      (node (ref "SW15") (pin "NO1") (pinfunction "NO1_NO1") (pintype "passive+no_connect"))
    )
    (net (code "197") (name "unconnected-(SW16-PadNO1)") (class "Default")
      (node (ref "SW16") (pin "NO1") (pinfunction "NO1_NO1") (pintype "passive+no_connect"))
    )
    (net (code "198") (name "unconnected-(SW17-PadNO1)") (class "Default")
      (node (ref "SW17") (pin "NO1") (pinfunction "NO1_NO1") (pintype "passive+no_connect"))
    )
    (net (code "199") (name "unconnected-(SW18-PadNO1)") (class "Default")
      (node (ref "SW18") (pin "NO1") (pinfunction "NO1_NO1") (pintype "passive+no_connect"))
    )
    (net (code "200") (name "unconnected-(SWcolor-PadNO1)") (class "Default")
      (node (ref "SWcolor") (pin "NO1") (pinfunction "NO1_NO1") (pintype "passive+no_connect"))
    )
    (net (code "201") (name "unconnected-(SWlcd-PadNO1)") (class "Default")
      (node (ref "SWlcd") (pin "NO1") (pinfunction "NO1_NO1") (pintype "passive+no_connect"))
    )
    (net (code "202") (name "unconnected-(TR_5V-on_off-Pad6)") (class "Default")
      (node (ref "TR_5V") (pin "6") (pinfunction "on_off_6") (pintype "passive+no_connect"))
    )
    (net (code "203") (name "unconnected-(TR_5V-trim-Pad4)") (class "Default")
      (node (ref "TR_5V") (pin "4") (pinfunction "trim_4") (pintype "passive+no_connect"))
    )
    (net (code "204") (name "unconnected-(YAHOURT-Pad7)") (class "Default")
      (node (ref "YAHOURT") (pin "7") (pinfunction "7_7") (pintype "passive+no_connect"))
    )
    (net (code "205") (name "unconnected-(YAHOURT-Pad14)") (class "Default")
      (node (ref "YAHOURT") (pin "14") (pinfunction "14_14") (pintype "passive+no_connect"))
    )
  )
)
